# homeboard11.net
KiCad netlist of a schematic drawn in EAGLE
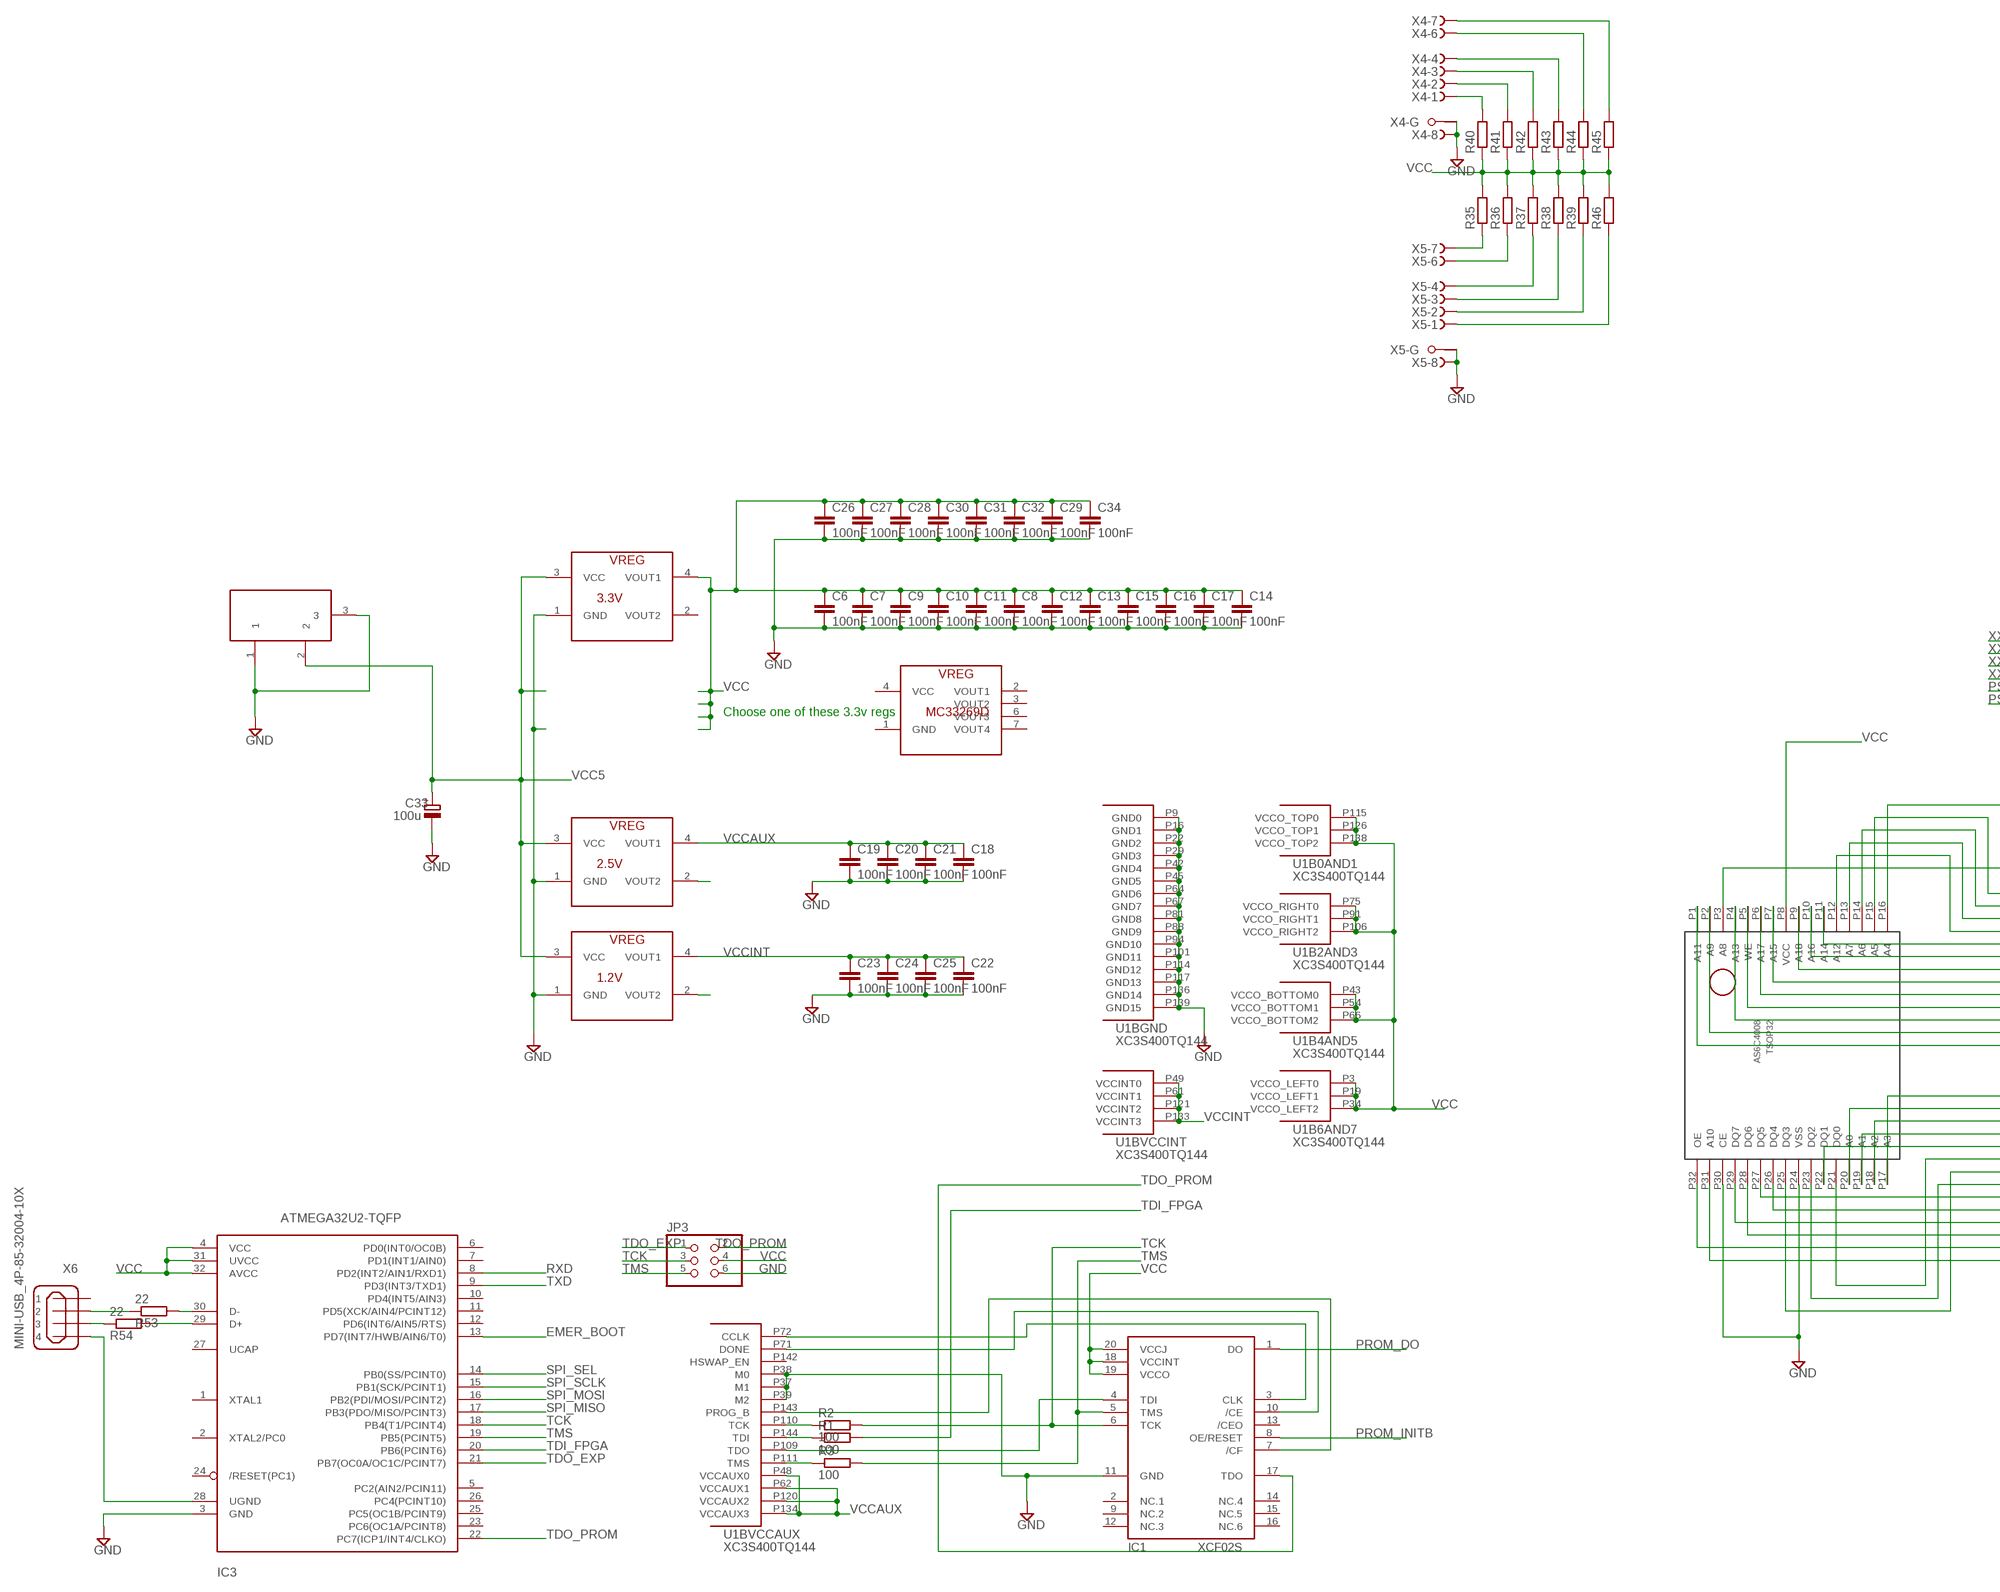
[diagram p0: schematic, sheet 1, part 1 of 3]
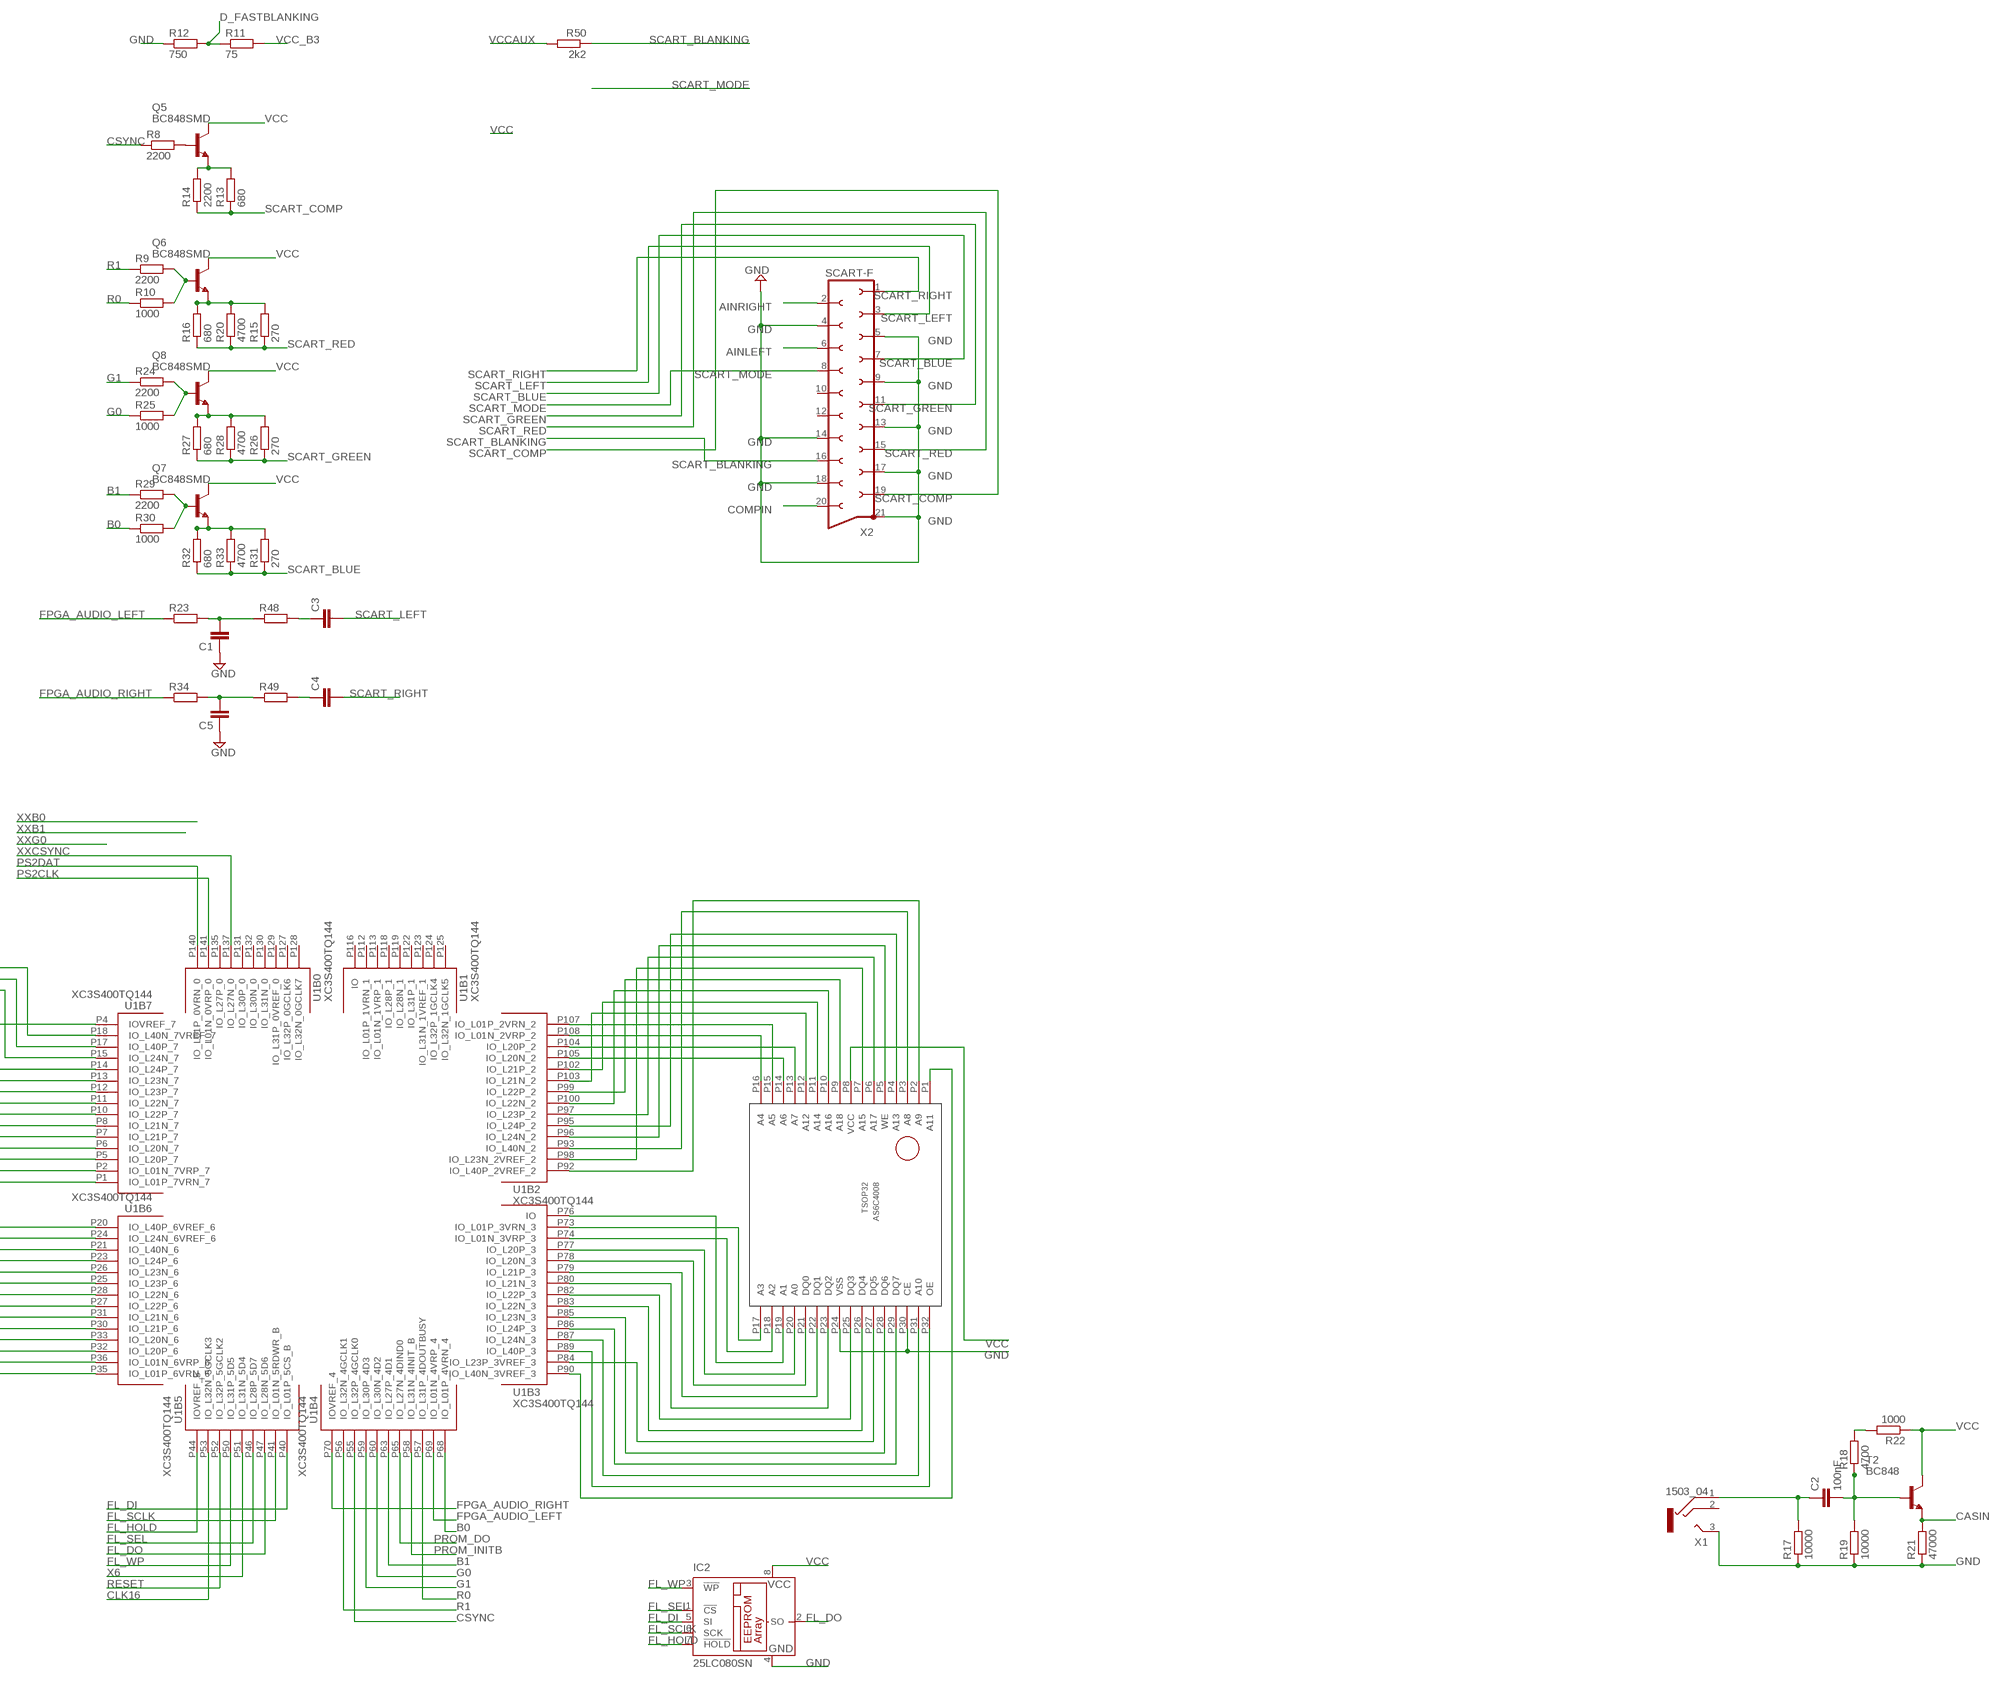
[diagram p1: schematic, sheet 1, part 2 of 3]
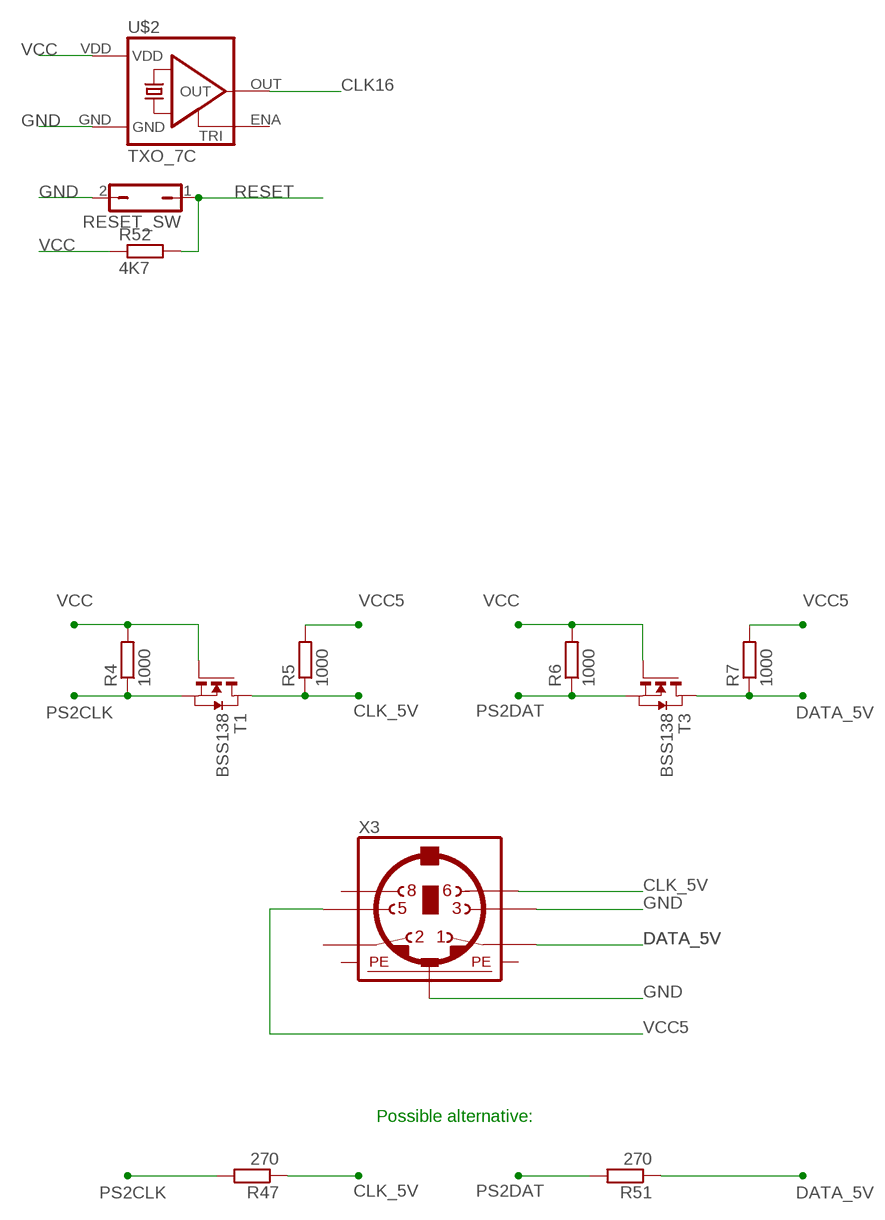
[diagram p2: schematic, sheet 1, part 3 of 3]

(export (version "E")
  (design (tool "Eeschema 10.0.6"))
  (components
    (comp (ref "C1")
      (value "C-EUC0603")
      (footprint "eagle-import:C0603")
      (libsource (lib "eagle-import") (part "resistor_C-EUC0603"))
    )
    (comp (ref "C2")
      (value "100nF")
      (footprint "eagle-import:C0603")
      (libsource (lib "eagle-import") (part "resistor_C-EUC0603"))
    )
    (comp (ref "C3")
      (value "C-EUC0603")
      (footprint "eagle-import:C0603")
      (libsource (lib "eagle-import") (part "resistor_C-EUC0603"))
    )
    (comp (ref "C4")
      (value "C-EUC0603")
      (footprint "eagle-import:C0603")
      (libsource (lib "eagle-import") (part "resistor_C-EUC0603"))
    )
    (comp (ref "C5")
      (value "C-EUC0603")
      (footprint "eagle-import:C0603")
      (libsource (lib "eagle-import") (part "resistor_C-EUC0603"))
    )
    (comp (ref "C6")
      (value "100nF")
      (footprint "eagle-import:C0603")
      (libsource (lib "eagle-import") (part "C-EUC0603"))
    )
    (comp (ref "C7")
      (value "100nF")
      (footprint "eagle-import:C0603")
      (libsource (lib "eagle-import") (part "C-EUC0603"))
    )
    (comp (ref "C8")
      (value "100nF")
      (footprint "eagle-import:C0603")
      (libsource (lib "eagle-import") (part "C-EUC0603"))
    )
    (comp (ref "C9")
      (value "100nF")
      (footprint "eagle-import:C0603")
      (libsource (lib "eagle-import") (part "C-EUC0603"))
    )
    (comp (ref "C10")
      (value "100nF")
      (footprint "eagle-import:C0603")
      (libsource (lib "eagle-import") (part "C-EUC0603"))
    )
    (comp (ref "C11")
      (value "100nF")
      (footprint "eagle-import:C0603")
      (libsource (lib "eagle-import") (part "C-EUC0603"))
    )
    (comp (ref "C12")
      (value "100nF")
      (footprint "eagle-import:C0603")
      (libsource (lib "eagle-import") (part "C-EUC0603"))
    )
    (comp (ref "C13")
      (value "100nF")
      (footprint "eagle-import:C0603")
      (libsource (lib "eagle-import") (part "C-EUC0603"))
    )
    (comp (ref "C14")
      (value "100nF")
      (footprint "eagle-import:C0603")
      (libsource (lib "eagle-import") (part "C-EUC0603"))
    )
    (comp (ref "C15")
      (value "100nF")
      (footprint "eagle-import:C0603")
      (libsource (lib "eagle-import") (part "C-EUC0603"))
    )
    (comp (ref "C16")
      (value "100nF")
      (footprint "eagle-import:C0603")
      (libsource (lib "eagle-import") (part "C-EUC0603"))
    )
    (comp (ref "C17")
      (value "100nF")
      (footprint "eagle-import:C0603")
      (libsource (lib "eagle-import") (part "C-EUC0603"))
    )
    (comp (ref "C18")
      (value "100nF")
      (footprint "eagle-import:C0603")
      (libsource (lib "eagle-import") (part "C-EUC0603"))
    )
    (comp (ref "C19")
      (value "100nF")
      (footprint "eagle-import:C0603")
      (libsource (lib "eagle-import") (part "C-EUC0603"))
    )
    (comp (ref "C20")
      (value "100nF")
      (footprint "eagle-import:C0603")
      (libsource (lib "eagle-import") (part "C-EUC0603"))
    )
    (comp (ref "C21")
      (value "100nF")
      (footprint "eagle-import:C0603")
      (libsource (lib "eagle-import") (part "C-EUC0603"))
    )
    (comp (ref "C22")
      (value "100nF")
      (footprint "eagle-import:C0603")
      (libsource (lib "eagle-import") (part "C-EUC0603"))
    )
    (comp (ref "C23")
      (value "100nF")
      (footprint "eagle-import:C0603")
      (libsource (lib "eagle-import") (part "C-EUC0603"))
    )
    (comp (ref "C24")
      (value "100nF")
      (footprint "eagle-import:C0603")
      (libsource (lib "eagle-import") (part "C-EUC0603"))
    )
    (comp (ref "C25")
      (value "100nF")
      (footprint "eagle-import:C0603")
      (libsource (lib "eagle-import") (part "C-EUC0603"))
    )
    (comp (ref "C26")
      (value "100nF")
      (footprint "eagle-import:C0603")
      (libsource (lib "eagle-import") (part "C-EUC0603"))
    )
    (comp (ref "C27")
      (value "100nF")
      (footprint "eagle-import:C0603")
      (libsource (lib "eagle-import") (part "C-EUC0603"))
    )
    (comp (ref "C28")
      (value "100nF")
      (footprint "eagle-import:C0603")
      (libsource (lib "eagle-import") (part "C-EUC0603"))
    )
    (comp (ref "C29")
      (value "100nF")
      (footprint "eagle-import:C0603")
      (libsource (lib "eagle-import") (part "C-EUC0603"))
    )
    (comp (ref "C30")
      (value "100nF")
      (footprint "eagle-import:C0603")
      (libsource (lib "eagle-import") (part "C-EUC0603"))
    )
    (comp (ref "C31")
      (value "100nF")
      (footprint "eagle-import:C0603")
      (libsource (lib "eagle-import") (part "C-EUC0603"))
    )
    (comp (ref "C32")
      (value "100nF")
      (footprint "eagle-import:C0603")
      (libsource (lib "eagle-import") (part "C-EUC0603"))
    )
    (comp (ref "C33")
      (value "100u")
      (footprint "eagle-import:PANASONIC_D")
      (libsource (lib "eagle-import") (part "CPOL-EUD"))
    )
    (comp (ref "C34")
      (value "100nF")
      (footprint "eagle-import:C0603")
      (libsource (lib "eagle-import") (part "C-EUC0603"))
    )
    (comp (ref "IC1")
      (value "XCF02S")
      (footprint "eagle-import:VO20")
      (libsource (lib "eagle-import") (part "XCF02S"))
    )
    (comp (ref "IC2")
      (value "25LC080SN")
      (footprint "eagle-import:SO-08")
      (fields (field (name "MF") "MICROCHIP") (field (name "MPN") "25LC080/SN"))
      (libsource (lib "eagle-import") (part "25SNLC080"))
    )
    (comp (ref "IC3")
      (value "ATMEGA32U2-TQFP")
      (footprint "eagle-import:TQFP32-08")
      (libsource (lib "eagle-import") (part "ATMEGA32U2-TQFP"))
    )
    (comp (ref "JP3")
      (value "PINHD-2X3")
      (footprint "eagle-import:2X03")
      (libsource (lib "eagle-import") (part "PINHD-2X3"))
    )
    (comp (ref "Q5")
      (value "BC848SMD")
      (footprint "eagle-import:SOT23")
      (libsource (lib "eagle-import") (part "BC848SMD"))
    )
    (comp (ref "Q6")
      (value "BC848SMD")
      (footprint "eagle-import:SOT23")
      (libsource (lib "eagle-import") (part "BC848SMD"))
    )
    (comp (ref "Q7")
      (value "BC848SMD")
      (footprint "eagle-import:SOT23")
      (libsource (lib "eagle-import") (part "BC848SMD"))
    )
    (comp (ref "Q8")
      (value "BC848SMD")
      (footprint "eagle-import:SOT23")
      (libsource (lib "eagle-import") (part "BC848SMD"))
    )
    (comp (ref "R1")
      (value "100")
      (footprint "eagle-import:R0805")
      (libsource (lib "eagle-import") (part "R-EU_R0805"))
    )
    (comp (ref "R2")
      (value "100")
      (footprint "eagle-import:R0805")
      (libsource (lib "eagle-import") (part "R-EU_R0805"))
    )
    (comp (ref "R3")
      (value "100")
      (footprint "eagle-import:R0805")
      (libsource (lib "eagle-import") (part "R-EU_R0805"))
    )
    (comp (ref "R4")
      (value "1000")
      (footprint "eagle-import:R0805")
      (libsource (lib "eagle-import") (part "R-EU_R0805"))
    )
    (comp (ref "R5")
      (value "1000")
      (footprint "eagle-import:R0805")
      (libsource (lib "eagle-import") (part "R-EU_R0805"))
    )
    (comp (ref "R6")
      (value "1000")
      (footprint "eagle-import:R0805")
      (libsource (lib "eagle-import") (part "R-EU_R0805"))
    )
    (comp (ref "R7")
      (value "1000")
      (footprint "eagle-import:R0805")
      (libsource (lib "eagle-import") (part "R-EU_R0805"))
    )
    (comp (ref "R8")
      (value "2200")
      (footprint "eagle-import:R0805")
      (libsource (lib "eagle-import") (part "R-EU_R0805"))
    )
    (comp (ref "R9")
      (value "2200")
      (footprint "eagle-import:R0805")
      (libsource (lib "eagle-import") (part "R-EU_R0805"))
    )
    (comp (ref "R10")
      (value "1000")
      (footprint "eagle-import:R0805")
      (libsource (lib "eagle-import") (part "R-EU_R0805"))
    )
    (comp (ref "R11")
      (value "75")
      (footprint "eagle-import:R0805")
      (libsource (lib "eagle-import") (part "R-EU_R0805"))
    )
    (comp (ref "R12")
      (value "750")
      (footprint "eagle-import:R0805")
      (libsource (lib "eagle-import") (part "R-EU_R0805"))
    )
    (comp (ref "R13")
      (value "680")
      (footprint "eagle-import:R0805")
      (libsource (lib "eagle-import") (part "R-EU_R0805"))
    )
    (comp (ref "R14")
      (value "2200")
      (footprint "eagle-import:R0805")
      (libsource (lib "eagle-import") (part "R-EU_R0805"))
    )
    (comp (ref "R15")
      (value "270")
      (footprint "eagle-import:R0805")
      (libsource (lib "eagle-import") (part "R-EU_R0805"))
    )
    (comp (ref "R16")
      (value "680")
      (footprint "eagle-import:R0805")
      (libsource (lib "eagle-import") (part "R-EU_R0805"))
    )
    (comp (ref "R17")
      (value "10000")
      (footprint "eagle-import:R0805")
      (libsource (lib "eagle-import") (part "R-EU_R0805"))
    )
    (comp (ref "R18")
      (value "4700")
      (footprint "eagle-import:R0805")
      (libsource (lib "eagle-import") (part "R-EU_R0805"))
    )
    (comp (ref "R19")
      (value "10000")
      (footprint "eagle-import:R0805")
      (libsource (lib "eagle-import") (part "R-EU_R0805"))
    )
    (comp (ref "R20")
      (value "4700")
      (footprint "eagle-import:R0805")
      (libsource (lib "eagle-import") (part "R-EU_R0805"))
    )
    (comp (ref "R21")
      (value "47000")
      (footprint "eagle-import:R0805")
      (libsource (lib "eagle-import") (part "R-EU_R0805"))
    )
    (comp (ref "R22")
      (value "1000")
      (footprint "eagle-import:R0805")
      (libsource (lib "eagle-import") (part "R-EU_R0805"))
    )
    (comp (ref "R23")
      (value "R-EU_M0805")
      (footprint "eagle-import:M0805")
      (libsource (lib "eagle-import") (part "resistor_R-EU_M0805"))
    )
    (comp (ref "R24")
      (value "2200")
      (footprint "eagle-import:R0805")
      (libsource (lib "eagle-import") (part "R-EU_R0805"))
    )
    (comp (ref "R25")
      (value "1000")
      (footprint "eagle-import:R0805")
      (libsource (lib "eagle-import") (part "R-EU_R0805"))
    )
    (comp (ref "R26")
      (value "270")
      (footprint "eagle-import:R0805")
      (libsource (lib "eagle-import") (part "R-EU_R0805"))
    )
    (comp (ref "R27")
      (value "680")
      (footprint "eagle-import:R0805")
      (libsource (lib "eagle-import") (part "R-EU_R0805"))
    )
    (comp (ref "R28")
      (value "4700")
      (footprint "eagle-import:R0805")
      (libsource (lib "eagle-import") (part "R-EU_R0805"))
    )
    (comp (ref "R29")
      (value "2200")
      (footprint "eagle-import:R0805")
      (libsource (lib "eagle-import") (part "R-EU_R0805"))
    )
    (comp (ref "R30")
      (value "1000")
      (footprint "eagle-import:R0805")
      (libsource (lib "eagle-import") (part "R-EU_R0805"))
    )
    (comp (ref "R31")
      (value "270")
      (footprint "eagle-import:R0805")
      (libsource (lib "eagle-import") (part "R-EU_R0805"))
    )
    (comp (ref "R32")
      (value "680")
      (footprint "eagle-import:R0805")
      (libsource (lib "eagle-import") (part "R-EU_R0805"))
    )
    (comp (ref "R33")
      (value "4700")
      (footprint "eagle-import:R0805")
      (libsource (lib "eagle-import") (part "R-EU_R0805"))
    )
    (comp (ref "R34")
      (value "R-EU_M0805")
      (footprint "eagle-import:M0805")
      (libsource (lib "eagle-import") (part "resistor_R-EU_M0805"))
    )
    (comp (ref "R35")
      (value "R-EU_M0805")
      (footprint "eagle-import:M0805")
      (libsource (lib "eagle-import") (part "resistor_R-EU_M0805"))
    )
    (comp (ref "R36")
      (value "R-EU_M0805")
      (footprint "eagle-import:M0805")
      (libsource (lib "eagle-import") (part "resistor_R-EU_M0805"))
    )
    (comp (ref "R37")
      (value "R-EU_M0805")
      (footprint "eagle-import:M0805")
      (libsource (lib "eagle-import") (part "resistor_R-EU_M0805"))
    )
    (comp (ref "R38")
      (value "R-EU_M0805")
      (footprint "eagle-import:M0805")
      (libsource (lib "eagle-import") (part "resistor_R-EU_M0805"))
    )
    (comp (ref "R39")
      (value "R-EU_M0805")
      (footprint "eagle-import:M0805")
      (libsource (lib "eagle-import") (part "resistor_R-EU_M0805"))
    )
    (comp (ref "R40")
      (value "R-EU_M0805")
      (footprint "eagle-import:M0805")
      (libsource (lib "eagle-import") (part "resistor_R-EU_M0805"))
    )
    (comp (ref "R41")
      (value "R-EU_M0805")
      (footprint "eagle-import:M0805")
      (libsource (lib "eagle-import") (part "resistor_R-EU_M0805"))
    )
    (comp (ref "R42")
      (value "R-EU_M0805")
      (footprint "eagle-import:M0805")
      (libsource (lib "eagle-import") (part "resistor_R-EU_M0805"))
    )
    (comp (ref "R43")
      (value "R-EU_M0805")
      (footprint "eagle-import:M0805")
      (libsource (lib "eagle-import") (part "resistor_R-EU_M0805"))
    )
    (comp (ref "R44")
      (value "R-EU_M0805")
      (footprint "eagle-import:M0805")
      (libsource (lib "eagle-import") (part "resistor_R-EU_M0805"))
    )
    (comp (ref "R45")
      (value "R-EU_M0805")
      (footprint "eagle-import:M0805")
      (libsource (lib "eagle-import") (part "resistor_R-EU_M0805"))
    )
    (comp (ref "R46")
      (value "R-EU_M0805")
      (footprint "eagle-import:M0805")
      (libsource (lib "eagle-import") (part "resistor_R-EU_M0805"))
    )
    (comp (ref "R47")
      (value "270")
      (footprint "eagle-import:R0805")
      (libsource (lib "eagle-import") (part "R-EU_R0805"))
    )
    (comp (ref "R48")
      (value "R-EU_M0805")
      (footprint "eagle-import:M0805")
      (libsource (lib "eagle-import") (part "resistor_R-EU_M0805"))
    )
    (comp (ref "R49")
      (value "R-EU_M0805")
      (footprint "eagle-import:M0805")
      (libsource (lib "eagle-import") (part "resistor_R-EU_M0805"))
    )
    (comp (ref "R50")
      (value "2k2")
      (footprint "eagle-import:M0805")
      (libsource (lib "eagle-import") (part "resistor_R-EU_M0805"))
    )
    (comp (ref "R51")
      (value "270")
      (footprint "eagle-import:R0805")
      (libsource (lib "eagle-import") (part "R-EU_R0805"))
    )
    (comp (ref "R52")
      (value "4K7")
      (footprint "eagle-import:M0805")
      (libsource (lib "eagle-import") (part "resistor_R-EU_M0805"))
    )
    (comp (ref "R53")
      (value "22")
      (footprint "eagle-import:R0805")
      (libsource (lib "eagle-import") (part "R-EU_R0805"))
    )
    (comp (ref "R54")
      (value "22")
      (footprint "eagle-import:R0805")
      (libsource (lib "eagle-import") (part "R-EU_R0805"))
    )
    (comp (ref "REG1.2")
      (value "1.2V")
      (footprint "eagle-import:SOT223")
      (libsource (lib "eagle-import") (part "NX1117"))
    )
    (comp (ref "REG2.5")
      (value "2.5V")
      (footprint "eagle-import:SOT223")
      (libsource (lib "eagle-import") (part "NX1117"))
    )
    (comp (ref "RESET_SW")
      (value "JP1Q")
      (footprint "eagle-import:JP1")
      (libsource (lib "eagle-import") (part "JP1Q"))
    )
    (comp (ref "T1")
      (value "BSS138")
      (footprint "eagle-import:SOT-23")
      (libsource (lib "eagle-import") (part "NMOSSOT23"))
    )
    (comp (ref "T2")
      (value "BC848")
      (footprint "eagle-import:SOT23")
      (libsource (lib "eagle-import") (part "BC848"))
    )
    (comp (ref "T3")
      (value "BSS138")
      (footprint "eagle-import:SOT-23")
      (libsource (lib "eagle-import") (part "NMOSSOT23"))
    )
    (comp (ref "U$1")
      (value "AS6C4008")
      (footprint "eagle-import:TSOP32")
      (libsource (lib "eagle-import") (part "AS6C4008"))
    )
    (comp (ref "U$2")
      (value "TXO_7C")
      (footprint "eagle-import:OSC_7C")
      (libsource (lib "eagle-import") (part "TXO_7C"))
    )
    (comp (ref "U$4")
      (value "3.3V")
      (footprint "eagle-import:SOT223")
      (libsource (lib "eagle-import") (part "NX1117"))
    )
    (comp (ref "U$5")
      (value "MC33269D")
      (footprint "eagle-import:SO8")
      (libsource (lib "eagle-import") (part "MC33269D"))
    )
    (comp (ref "U$6")
      (value "AS6C4008")
      (footprint "eagle-import:TSOP32")
      (libsource (lib "eagle-import") (part "AS6C4008"))
    )
    (comp (ref "U1")
      (value "XC3S400TQ144")
      (footprint "eagle-import:TQ144")
      (libsource (lib "eagle-import") (part "XC3S400TQ144"))
    )
    (comp (ref "X1")
      (value "1503_04")
      (footprint "eagle-import:1503_04")
      (libsource (lib "eagle-import") (part "1503_04"))
    )
    (comp (ref "X2")
      (value "SCART-F")
      (footprint "eagle-import:SCART-F")
      (libsource (lib "eagle-import") (part "SCART-F"))
    )
    (comp (ref "X3")
      (value "MINI_DIN_6")
      (footprint "eagle-import:M_DIN6")
      (libsource (lib "eagle-import") (part "MINI_DIN_6"))
    )
    (comp (ref "X4")
      (value "F09HPS")
      (footprint "eagle-import:F09HP")
      (libsource (lib "eagle-import") (part "F09HPS"))
    )
    (comp (ref "X5")
      (value "F09HPS")
      (footprint "eagle-import:F09HP")
      (libsource (lib "eagle-import") (part "F09HPS"))
    )
    (comp (ref "X6")
      (value "MINI-USB_4P-85-32004-10X")
      (footprint "eagle-import:85-32004-10X")
      (libsource (lib "eagle-import") (part "MINI-USB_4P-85-32004-10X"))
    )
    (comp (ref "X8")
      (value "DC21MMX")
      (footprint "eagle-import:DC-21MM")
      (libsource (lib "eagle-import") (part "DC21MMX"))
    )
  )
  (nets
    (net (code "1") (name "/AINLEFT") (class "Default")
      (node (ref "X2") (pin "6") (pinfunction "6_6") (pintype "passive"))
    )
    (net (code "2") (name "/AINRIGHT") (class "Default")
      (node (ref "X2") (pin "2") (pinfunction "2_2") (pintype "passive"))
    )
    (net (code "3") (name "/B0") (class "Default")
      (node (ref "R30") (pin "1") (pinfunction "1_1") (pintype "passive"))
      (node (ref "U1") (pin "P68") (pinfunction "IO_L01P_4VRN_4_P68") (pintype "bidirectional"))
    )
    (net (code "4") (name "/B1") (class "Default")
      (node (ref "R29") (pin "1") (pinfunction "1_1") (pintype "passive"))
      (node (ref "U1") (pin "P63") (pinfunction "IO_L27P_4D1_P63") (pintype "bidirectional"))
    )
    (net (code "5") (name "/CASIN") (class "Default")
      (node (ref "R21") (pin "2") (pinfunction "2_2") (pintype "passive"))
      (node (ref "T2") (pin "2") (pinfunction "E_2") (pintype "passive"))
    )
    (net (code "6") (name "/CLK16") (class "Default")
      (node (ref "U$2") (pin "OUT") (pinfunction "OUT_OUT") (pintype "output"))
      (node (ref "U1") (pin "P53") (pinfunction "IO_L32N_5GCLK3_P53") (pintype "bidirectional"))
    )
    (net (code "7") (name "/CLK_5V") (class "Default")
      (node (ref "R47") (pin "1") (pinfunction "1_1") (pintype "passive"))
      (node (ref "R5") (pin "1") (pinfunction "1_1") (pintype "passive"))
      (node (ref "T1") (pin "1") (pinfunction "D_1") (pintype "passive"))
      (node (ref "X3") (pin "6") (pinfunction "6_6") (pintype "passive"))
    )
    (net (code "8") (name "/COMPIN") (class "Default")
      (node (ref "X2") (pin "20") (pinfunction "20_20") (pintype "passive"))
    )
    (net (code "9") (name "/CSYNC") (class "Default")
      (node (ref "R8") (pin "1") (pinfunction "1_1") (pintype "passive"))
      (node (ref "U1") (pin "P55") (pinfunction "IO_L32P_4GCLK0_P55") (pintype "bidirectional"))
    )
    (net (code "10") (name "/DATA_5V") (class "Default")
      (node (ref "R51") (pin "1") (pinfunction "1_1") (pintype "passive"))
      (node (ref "R7") (pin "1") (pinfunction "1_1") (pintype "passive"))
      (node (ref "T3") (pin "1") (pinfunction "D_1") (pintype "passive"))
      (node (ref "X3") (pin "1") (pinfunction "1_1") (pintype "passive"))
    )
    (net (code "11") (name "/D_FASTBLANKING") (class "Default")
      (node (ref "R11") (pin "1") (pinfunction "1_1") (pintype "passive"))
      (node (ref "R12") (pin "2") (pinfunction "2_2") (pintype "passive"))
    )
    (net (code "12") (name "/EMER_BOOT") (class "Default")
      (node (ref "IC3") (pin "13") (pinfunction "PD7(INT7/HWB/AIN6/T0)_13") (pintype "bidirectional"))
    )
    (net (code "13") (name "/FL_DI") (class "Default")
      (node (ref "IC2") (pin "5") (pinfunction "SI_5") (pintype "input"))
      (node (ref "U1") (pin "P40") (pinfunction "IO_L01P_5CS_B_P40") (pintype "bidirectional"))
    )
    (net (code "14") (name "/FL_DO") (class "Default")
      (node (ref "IC2") (pin "2") (pinfunction "SO_2") (pintype "bidirectional"))
      (node (ref "U1") (pin "P47") (pinfunction "IO_L28N_5D6_P47") (pintype "bidirectional"))
    )
    (net (code "15") (name "/FL_HOLD") (class "Default")
      (node (ref "IC2") (pin "7") (pinfunction "~{HOLD}_7") (pintype "input"))
      (node (ref "U1") (pin "P44") (pinfunction "IOVREF_5_P44") (pintype "bidirectional"))
    )
    (net (code "16") (name "/FL_SCLK") (class "Default")
      (node (ref "IC2") (pin "6") (pinfunction "SCK_6") (pintype "input"))
      (node (ref "U1") (pin "P41") (pinfunction "IO_L01N_5RDWR_B_P41") (pintype "bidirectional"))
    )
    (net (code "17") (name "/FL_SEL") (class "Default")
      (node (ref "IC2") (pin "1") (pinfunction "~{CS}_1") (pintype "input"))
      (node (ref "U1") (pin "P46") (pinfunction "IO_L28P_5D7_P46") (pintype "bidirectional"))
    )
    (net (code "18") (name "/FL_WP") (class "Default")
      (node (ref "IC2") (pin "3") (pinfunction "~{WP}_3") (pintype "input"))
      (node (ref "U1") (pin "P50") (pinfunction "IO_L31P_5D5_P50") (pintype "bidirectional"))
    )
    (net (code "19") (name "/FPGA_AUDIO_LEFT") (class "Default")
      (node (ref "R23") (pin "1") (pinfunction "1_1") (pintype "passive"))
      (node (ref "U1") (pin "P69") (pinfunction "IO_L01N_4VRP_4_P69") (pintype "bidirectional"))
    )
    (net (code "20") (name "/FPGA_AUDIO_RIGHT") (class "Default")
      (node (ref "R34") (pin "1") (pinfunction "1_1") (pintype "passive"))
      (node (ref "U1") (pin "P70") (pinfunction "IOVREF_4_P70") (pintype "bidirectional"))
    )
    (net (code "21") (name "/G0") (class "Default")
      (node (ref "R25") (pin "1") (pinfunction "1_1") (pintype "passive"))
      (node (ref "U1") (pin "P60") (pinfunction "IO_L30N_4D2_P60") (pintype "bidirectional"))
    )
    (net (code "22") (name "/G1") (class "Default")
      (node (ref "R24") (pin "1") (pinfunction "1_1") (pintype "passive"))
      (node (ref "U1") (pin "P59") (pinfunction "IO_L30P_4D3_P59") (pintype "bidirectional"))
    )
    (net (code "23") (name "/PE1") (class "Default")
      (node (ref "X3") (pin "SH1") (pinfunction "PE1_SH1") (pintype "power_in"))
    )
    (net (code "24") (name "/PE3") (class "Default")
      (node (ref "X3") (pin "SH3") (pinfunction "PE3_SH3") (pintype "power_in"))
    )
    (net (code "25") (name "/PROM_DO") (class "Default")
      (node (ref "IC1") (pin "1") (pinfunction "DO_1") (pintype "bidirectional"))
      (node (ref "U1") (pin "P65") (pinfunction "IO_L27N_4DIND0_P65") (pintype "bidirectional"))
    )
    (net (code "26") (name "/PROM_INITB") (class "Default")
      (node (ref "IC1") (pin "8") (pinfunction "OE/RESET_8") (pintype "bidirectional"))
      (node (ref "U1") (pin "P58") (pinfunction "IO_L31N_4INIT_B_P58") (pintype "bidirectional"))
    )
    (net (code "27") (name "/PS2CLK") (class "Default")
      (node (ref "R4") (pin "1") (pinfunction "1_1") (pintype "passive"))
      (node (ref "R47") (pin "2") (pinfunction "2_2") (pintype "passive"))
      (node (ref "T1") (pin "2") (pinfunction "S_2") (pintype "passive"))
      (node (ref "U1") (pin "P141") (pinfunction "IO_L01N_0VRP_0_P141") (pintype "bidirectional"))
    )
    (net (code "28") (name "/PS2DAT") (class "Default")
      (node (ref "R51") (pin "2") (pinfunction "2_2") (pintype "passive"))
      (node (ref "R6") (pin "1") (pinfunction "1_1") (pintype "passive"))
      (node (ref "T3") (pin "2") (pinfunction "S_2") (pintype "passive"))
      (node (ref "U1") (pin "P140") (pinfunction "IO_L01P_0VRN_0_P140") (pintype "bidirectional"))
    )
    (net (code "29") (name "/R0") (class "Default")
      (node (ref "R10") (pin "1") (pinfunction "1_1") (pintype "passive"))
      (node (ref "U1") (pin "P57") (pinfunction "IO_L31P_4DOUTBUSY_P57") (pintype "bidirectional"))
    )
    (net (code "30") (name "/R1") (class "Default")
      (node (ref "R9") (pin "1") (pinfunction "1_1") (pintype "passive"))
      (node (ref "U1") (pin "P56") (pinfunction "IO_L32N_4GCLK1_P56") (pintype "bidirectional"))
    )
    (net (code "31") (name "/RESET") (class "Default")
      (node (ref "R52") (pin "2") (pinfunction "2_2") (pintype "passive"))
      (node (ref "RESET_SW") (pin "1") (pinfunction "1_1") (pintype "passive"))
      (node (ref "U1") (pin "P52") (pinfunction "IO_L32P_5GCLK2_P52") (pintype "bidirectional"))
    )
    (net (code "32") (name "/RXD") (class "Default")
      (node (ref "IC3") (pin "8") (pinfunction "PD2(INT2/AIN1/RXD1)_8") (pintype "bidirectional"))
    )
    (net (code "33") (name "/SCART_BLANKING") (class "Default")
      (node (ref "R50") (pin "1") (pinfunction "1_1") (pintype "passive"))
      (node (ref "X2") (pin "16") (pinfunction "16_16") (pintype "passive"))
    )
    (net (code "34") (name "/SCART_BLUE") (class "Default")
      (node (ref "R31") (pin "1") (pinfunction "1_1") (pintype "passive"))
      (node (ref "R32") (pin "1") (pinfunction "1_1") (pintype "passive"))
      (node (ref "R33") (pin "1") (pinfunction "1_1") (pintype "passive"))
      (node (ref "X2") (pin "7") (pinfunction "7_7") (pintype "passive"))
    )
    (net (code "35") (name "/SCART_COMP") (class "Default")
      (node (ref "R13") (pin "1") (pinfunction "1_1") (pintype "passive"))
      (node (ref "R14") (pin "1") (pinfunction "1_1") (pintype "passive"))
      (node (ref "X2") (pin "19") (pinfunction "19_19") (pintype "passive"))
    )
    (net (code "36") (name "/SCART_GREEN") (class "Default")
      (node (ref "R26") (pin "1") (pinfunction "1_1") (pintype "passive"))
      (node (ref "R27") (pin "1") (pinfunction "1_1") (pintype "passive"))
      (node (ref "R28") (pin "1") (pinfunction "1_1") (pintype "passive"))
      (node (ref "X2") (pin "11") (pinfunction "11_11") (pintype "passive"))
    )
    (net (code "37") (name "/SCART_LEFT") (class "Default")
      (node (ref "C3") (pin "2") (pinfunction "2_2") (pintype "passive"))
      (node (ref "X2") (pin "3") (pinfunction "3_3") (pintype "passive"))
    )
    (net (code "38") (name "/SCART_MODE") (class "Default")
      (node (ref "X2") (pin "8") (pinfunction "8_8") (pintype "passive"))
    )
    (net (code "39") (name "/SCART_RED") (class "Default")
      (node (ref "R15") (pin "1") (pinfunction "1_1") (pintype "passive"))
      (node (ref "R16") (pin "1") (pinfunction "1_1") (pintype "passive"))
      (node (ref "R20") (pin "1") (pinfunction "1_1") (pintype "passive"))
      (node (ref "X2") (pin "15") (pinfunction "15_15") (pintype "passive"))
    )
    (net (code "40") (name "/SCART_RIGHT") (class "Default")
      (node (ref "C4") (pin "2") (pinfunction "2_2") (pintype "passive"))
      (node (ref "X2") (pin "1") (pinfunction "1_1") (pintype "passive"))
    )
    (net (code "41") (name "/SPI_MISO") (class "Default")
      (node (ref "IC3") (pin "17") (pinfunction "PB3(PDO/MISO/PCINT3)_17") (pintype "bidirectional"))
    )
    (net (code "42") (name "/SPI_MOSI") (class "Default")
      (node (ref "IC3") (pin "16") (pinfunction "PB2(PDI/MOSI/PCINT2)_16") (pintype "bidirectional"))
    )
    (net (code "43") (name "/SPI_SCLK") (class "Default")
      (node (ref "IC3") (pin "15") (pinfunction "PB1(SCK/PCINT1)_15") (pintype "bidirectional"))
    )
    (net (code "44") (name "/SPI_SEL") (class "Default")
      (node (ref "IC3") (pin "14") (pinfunction "PB0(SS/PCINT0)_14") (pintype "bidirectional"))
    )
    (net (code "45") (name "/TCK") (class "Default")
      (node (ref "IC1") (pin "6") (pinfunction "TCK_6") (pintype "bidirectional"))
      (node (ref "IC3") (pin "18") (pinfunction "PB4(T1/PCINT4)_18") (pintype "bidirectional"))
      (node (ref "JP3") (pin "3") (pinfunction "3_3") (pintype "passive"))
      (node (ref "R2") (pin "2") (pinfunction "2_2") (pintype "passive"))
    )
    (net (code "46") (name "/TDI_FPGA") (class "Default")
      (node (ref "IC3") (pin "20") (pinfunction "PB6(PCINT6)_20") (pintype "bidirectional"))
      (node (ref "R1") (pin "2") (pinfunction "2_2") (pintype "passive"))
    )
    (net (code "47") (name "/TDO_EXP") (class "Default")
      (node (ref "IC3") (pin "21") (pinfunction "PB7(OC0A/OC1C/PCINT7)_21") (pintype "bidirectional"))
      (node (ref "JP3") (pin "1") (pinfunction "1_1") (pintype "passive"))
    )
    (net (code "48") (name "/TDO_PROM") (class "Default")
      (node (ref "IC1") (pin "17") (pinfunction "TDO_17") (pintype "bidirectional"))
      (node (ref "IC3") (pin "22") (pinfunction "PC7(ICP1/INT4/CLKO)_22") (pintype "bidirectional"))
      (node (ref "JP3") (pin "2") (pinfunction "2_2") (pintype "passive"))
    )
    (net (code "49") (name "/TMS") (class "Default")
      (node (ref "IC1") (pin "5") (pinfunction "TMS_5") (pintype "bidirectional"))
      (node (ref "IC3") (pin "19") (pinfunction "PB5(PCINT5)_19") (pintype "bidirectional"))
      (node (ref "JP3") (pin "5") (pinfunction "5_5") (pintype "passive"))
      (node (ref "R3") (pin "2") (pinfunction "2_2") (pintype "passive"))
    )
    (net (code "50") (name "/TXD") (class "Default")
      (node (ref "IC3") (pin "9") (pinfunction "PD3(INT3/TXD1)_9") (pintype "bidirectional"))
    )
    (net (code "51") (name "/VCC") (class "Default")
      (node (ref "C10") (pin "1") (pinfunction "1_1") (pintype "passive"))
      (node (ref "C11") (pin "1") (pinfunction "1_1") (pintype "passive"))
      (node (ref "C12") (pin "1") (pinfunction "1_1") (pintype "passive"))
      (node (ref "C13") (pin "1") (pinfunction "1_1") (pintype "passive"))
      (node (ref "C14") (pin "1") (pinfunction "1_1") (pintype "passive"))
      (node (ref "C15") (pin "1") (pinfunction "1_1") (pintype "passive"))
      (node (ref "C16") (pin "1") (pinfunction "1_1") (pintype "passive"))
      (node (ref "C17") (pin "1") (pinfunction "1_1") (pintype "passive"))
      (node (ref "C26") (pin "1") (pinfunction "1_1") (pintype "passive"))
      (node (ref "C27") (pin "1") (pinfunction "1_1") (pintype "passive"))
      (node (ref "C28") (pin "1") (pinfunction "1_1") (pintype "passive"))
      (node (ref "C29") (pin "1") (pinfunction "1_1") (pintype "passive"))
      (node (ref "C30") (pin "1") (pinfunction "1_1") (pintype "passive"))
      (node (ref "C31") (pin "1") (pinfunction "1_1") (pintype "passive"))
      (node (ref "C32") (pin "1") (pinfunction "1_1") (pintype "passive"))
      (node (ref "C34") (pin "1") (pinfunction "1_1") (pintype "passive"))
      (node (ref "C6") (pin "1") (pinfunction "1_1") (pintype "passive"))
      (node (ref "C7") (pin "1") (pinfunction "1_1") (pintype "passive"))
      (node (ref "C8") (pin "1") (pinfunction "1_1") (pintype "passive"))
      (node (ref "C9") (pin "1") (pinfunction "1_1") (pintype "passive"))
      (node (ref "IC1") (pin "18") (pinfunction "VCCINT_18") (pintype "bidirectional"))
      (node (ref "IC1") (pin "19") (pinfunction "VCCO_19") (pintype "bidirectional"))
      (node (ref "IC1") (pin "20") (pinfunction "VCCJ_20") (pintype "bidirectional"))
      (node (ref "IC2") (pin "8") (pinfunction "VCC_8") (pintype "power_in"))
      (node (ref "IC3") (pin "31") (pinfunction "UVCC_31") (pintype "bidirectional"))
      (node (ref "IC3") (pin "32") (pinfunction "AVCC_32") (pintype "bidirectional"))
      (node (ref "IC3") (pin "4") (pinfunction "VCC_4") (pintype "bidirectional"))
      (node (ref "JP3") (pin "4") (pinfunction "4_4") (pintype "passive"))
      (node (ref "Q5") (pin "3") (pinfunction "C_3") (pintype "passive"))
      (node (ref "Q6") (pin "3") (pinfunction "C_3") (pintype "passive"))
      (node (ref "Q7") (pin "3") (pinfunction "C_3") (pintype "passive"))
      (node (ref "Q8") (pin "3") (pinfunction "C_3") (pintype "passive"))
      (node (ref "R22") (pin "1") (pinfunction "1_1") (pintype "passive"))
      (node (ref "R35") (pin "2") (pinfunction "2_2") (pintype "passive"))
      (node (ref "R36") (pin "2") (pinfunction "2_2") (pintype "passive"))
      (node (ref "R37") (pin "2") (pinfunction "2_2") (pintype "passive"))
      (node (ref "R38") (pin "2") (pinfunction "2_2") (pintype "passive"))
      (node (ref "R39") (pin "2") (pinfunction "2_2") (pintype "passive"))
      (node (ref "R4") (pin "2") (pinfunction "2_2") (pintype "passive"))
      (node (ref "R40") (pin "1") (pinfunction "1_1") (pintype "passive"))
      (node (ref "R41") (pin "1") (pinfunction "1_1") (pintype "passive"))
      (node (ref "R42") (pin "1") (pinfunction "1_1") (pintype "passive"))
      (node (ref "R43") (pin "1") (pinfunction "1_1") (pintype "passive"))
      (node (ref "R44") (pin "1") (pinfunction "1_1") (pintype "passive"))
      (node (ref "R45") (pin "1") (pinfunction "1_1") (pintype "passive"))
      (node (ref "R46") (pin "2") (pinfunction "2_2") (pintype "passive"))
      (node (ref "R52") (pin "1") (pinfunction "1_1") (pintype "passive"))
      (node (ref "R6") (pin "2") (pinfunction "2_2") (pintype "passive"))
      (node (ref "T1") (pin "3") (pinfunction "G_3") (pintype "passive"))
      (node (ref "T2") (pin "3") (pinfunction "C_3") (pintype "passive"))
      (node (ref "T3") (pin "3") (pinfunction "G_3") (pintype "passive"))
      (node (ref "U$1") (pin "P8") (pinfunction "VCC_P8") (pintype "bidirectional"))
      (node (ref "U$2") (pin "VDD") (pinfunction "VDD_VDD") (pintype "power_in"))
      (node (ref "U$4") (pin "4") (pinfunction "VOUT1_4") (pintype "bidirectional"))
      (node (ref "U$6") (pin "P8") (pinfunction "VCC_P8") (pintype "bidirectional"))
      (node (ref "U1") (pin "P106") (pinfunction "VCCO_RIGHT2_P106") (pintype "passive"))
      (node (ref "U1") (pin "P115") (pinfunction "VCCO_TOP0_P115") (pintype "passive"))
      (node (ref "U1") (pin "P126") (pinfunction "VCCO_TOP1_P126") (pintype "passive"))
      (node (ref "U1") (pin "P138") (pinfunction "VCCO_TOP2_P138") (pintype "passive"))
      (node (ref "U1") (pin "P19") (pinfunction "VCCO_LEFT1_P19") (pintype "passive"))
      (node (ref "U1") (pin "P3") (pinfunction "VCCO_LEFT0_P3") (pintype "passive"))
      (node (ref "U1") (pin "P34") (pinfunction "VCCO_LEFT2_P34") (pintype "passive"))
      (node (ref "U1") (pin "P43") (pinfunction "VCCO_BOTTOM0_P43") (pintype "passive"))
      (node (ref "U1") (pin "P54") (pinfunction "VCCO_BOTTOM1_P54") (pintype "passive"))
      (node (ref "U1") (pin "P66") (pinfunction "VCCO_BOTTOM2_P66") (pintype "passive"))
      (node (ref "U1") (pin "P75") (pinfunction "VCCO_RIGHT0_P75") (pintype "passive"))
      (node (ref "U1") (pin "P91") (pinfunction "VCCO_RIGHT1_P91") (pintype "passive"))
    )
    (net (code "52") (name "/VCC5") (class "Default")
      (node (ref "C33") (pin "+") (pinfunction "+_+") (pintype "passive"))
      (node (ref "R5") (pin "2") (pinfunction "2_2") (pintype "passive"))
      (node (ref "R7") (pin "2") (pinfunction "2_2") (pintype "passive"))
      (node (ref "REG1.2") (pin "3") (pinfunction "VCC_3") (pintype "bidirectional"))
      (node (ref "REG2.5") (pin "3") (pinfunction "VCC_3") (pintype "bidirectional"))
      (node (ref "U$4") (pin "3") (pinfunction "VCC_3") (pintype "bidirectional"))
      (node (ref "X3") (pin "5") (pinfunction "5_5") (pintype "passive"))
      (node (ref "X8") (pin "2") (pinfunction "2_2") (pintype "power_in"))
    )
    (net (code "53") (name "/VCCAUX") (class "Default")
      (node (ref "C18") (pin "1") (pinfunction "1_1") (pintype "passive"))
      (node (ref "C19") (pin "1") (pinfunction "1_1") (pintype "passive"))
      (node (ref "C20") (pin "1") (pinfunction "1_1") (pintype "passive"))
      (node (ref "C21") (pin "1") (pinfunction "1_1") (pintype "passive"))
      (node (ref "R50") (pin "2") (pinfunction "2_2") (pintype "passive"))
      (node (ref "REG2.5") (pin "4") (pinfunction "VOUT1_4") (pintype "bidirectional"))
      (node (ref "U1") (pin "P120") (pinfunction "VCCAUX2_P120") (pintype "passive"))
      (node (ref "U1") (pin "P134") (pinfunction "VCCAUX3_P134") (pintype "passive"))
      (node (ref "U1") (pin "P48") (pinfunction "VCCAUX0_P48") (pintype "passive"))
      (node (ref "U1") (pin "P62") (pinfunction "VCCAUX1_P62") (pintype "passive"))
    )
    (net (code "54") (name "/VCCINT") (class "Default")
      (node (ref "C22") (pin "1") (pinfunction "1_1") (pintype "passive"))
      (node (ref "C23") (pin "1") (pinfunction "1_1") (pintype "passive"))
      (node (ref "C24") (pin "1") (pinfunction "1_1") (pintype "passive"))
      (node (ref "C25") (pin "1") (pinfunction "1_1") (pintype "passive"))
      (node (ref "REG1.2") (pin "4") (pinfunction "VOUT1_4") (pintype "bidirectional"))
      (node (ref "U1") (pin "P121") (pinfunction "VCCINT2_P121") (pintype "passive"))
      (node (ref "U1") (pin "P133") (pinfunction "VCCINT3_P133") (pintype "passive"))
      (node (ref "U1") (pin "P49") (pinfunction "VCCINT0_P49") (pintype "passive"))
      (node (ref "U1") (pin "P61") (pinfunction "VCCINT1_P61") (pintype "passive"))
    )
    (net (code "55") (name "/VCC_B3") (class "Default")
      (node (ref "R11") (pin "2") (pinfunction "2_2") (pintype "passive"))
    )
    (net (code "56") (name "/X6") (class "Default")
      (node (ref "U1") (pin "P51") (pinfunction "IO_L31N_5D4_P51") (pintype "bidirectional"))
    )
    (net (code "59") (name "/XXCSYNC") (class "Default")
      (node (ref "U1") (pin "P137") (pinfunction "IO_L27N_0_P137") (pintype "bidirectional"))
    )
    (net (code "61") (name "GND") (class "Default")
      (node (ref "C1") (pin "1") (pinfunction "1_1") (pintype "passive"))
      (node (ref "C10") (pin "2") (pinfunction "2_2") (pintype "passive"))
      (node (ref "C11") (pin "2") (pinfunction "2_2") (pintype "passive"))
      (node (ref "C12") (pin "2") (pinfunction "2_2") (pintype "passive"))
      (node (ref "C13") (pin "2") (pinfunction "2_2") (pintype "passive"))
      (node (ref "C14") (pin "2") (pinfunction "2_2") (pintype "passive"))
      (node (ref "C15") (pin "2") (pinfunction "2_2") (pintype "passive"))
      (node (ref "C16") (pin "2") (pinfunction "2_2") (pintype "passive"))
      (node (ref "C17") (pin "2") (pinfunction "2_2") (pintype "passive"))
      (node (ref "C18") (pin "2") (pinfunction "2_2") (pintype "passive"))
      (node (ref "C19") (pin "2") (pinfunction "2_2") (pintype "passive"))
      (node (ref "C20") (pin "2") (pinfunction "2_2") (pintype "passive"))
      (node (ref "C21") (pin "2") (pinfunction "2_2") (pintype "passive"))
      (node (ref "C22") (pin "2") (pinfunction "2_2") (pintype "passive"))
      (node (ref "C23") (pin "2") (pinfunction "2_2") (pintype "passive"))
      (node (ref "C24") (pin "2") (pinfunction "2_2") (pintype "passive"))
      (node (ref "C25") (pin "2") (pinfunction "2_2") (pintype "passive"))
      (node (ref "C26") (pin "2") (pinfunction "2_2") (pintype "passive"))
      (node (ref "C27") (pin "2") (pinfunction "2_2") (pintype "passive"))
      (node (ref "C28") (pin "2") (pinfunction "2_2") (pintype "passive"))
      (node (ref "C29") (pin "2") (pinfunction "2_2") (pintype "passive"))
      (node (ref "C30") (pin "2") (pinfunction "2_2") (pintype "passive"))
      (node (ref "C31") (pin "2") (pinfunction "2_2") (pintype "passive"))
      (node (ref "C32") (pin "2") (pinfunction "2_2") (pintype "passive"))
      (node (ref "C33") (pin "-") (pinfunction "-_-") (pintype "passive"))
      (node (ref "C34") (pin "2") (pinfunction "2_2") (pintype "passive"))
      (node (ref "C5") (pin "1") (pinfunction "1_1") (pintype "passive"))
      (node (ref "C6") (pin "2") (pinfunction "2_2") (pintype "passive"))
      (node (ref "C7") (pin "2") (pinfunction "2_2") (pintype "passive"))
      (node (ref "C8") (pin "2") (pinfunction "2_2") (pintype "passive"))
      (node (ref "C9") (pin "2") (pinfunction "2_2") (pintype "passive"))
      (node (ref "IC1") (pin "11") (pinfunction "GND_11") (pintype "bidirectional"))
      (node (ref "IC2") (pin "4") (pinfunction "GND_4") (pintype "power_in"))
      (node (ref "IC3") (pin "3") (pinfunction "GND_3") (pintype "bidirectional"))
      (node (ref "JP3") (pin "6") (pinfunction "6_6") (pintype "passive"))
      (node (ref "R12") (pin "1") (pinfunction "1_1") (pintype "passive"))
      (node (ref "R17") (pin "1") (pinfunction "1_1") (pintype "passive"))
      (node (ref "R19") (pin "1") (pinfunction "1_1") (pintype "passive"))
      (node (ref "R21") (pin "1") (pinfunction "1_1") (pintype "passive"))
      (node (ref "REG1.2") (pin "1") (pinfunction "GND_1") (pintype "bidirectional"))
      (node (ref "REG2.5") (pin "1") (pinfunction "GND_1") (pintype "bidirectional"))
      (node (ref "RESET_SW") (pin "2") (pinfunction "2_2") (pintype "passive"))
      (node (ref "U$1") (pin "P24") (pinfunction "VSS_P24") (pintype "bidirectional"))
      (node (ref "U$1") (pin "P30") (pinfunction "CE_P30") (pintype "bidirectional"))
      (node (ref "U$2") (pin "GND") (pinfunction "GND_GND") (pintype "power_in"))
      (node (ref "U$4") (pin "1") (pinfunction "GND_1") (pintype "bidirectional"))
      (node (ref "U$6") (pin "P24") (pinfunction "VSS_P24") (pintype "bidirectional"))
      (node (ref "U$6") (pin "P30") (pinfunction "CE_P30") (pintype "bidirectional"))
      (node (ref "U1") (pin "P101") (pinfunction "GND11_P101") (pintype "passive"))
      (node (ref "U1") (pin "P114") (pinfunction "GND12_P114") (pintype "passive"))
      (node (ref "U1") (pin "P117") (pinfunction "GND13_P117") (pintype "passive"))
      (node (ref "U1") (pin "P136") (pinfunction "GND14_P136") (pintype "passive"))
      (node (ref "U1") (pin "P139") (pinfunction "GND15_P139") (pintype "passive"))
      (node (ref "U1") (pin "P16") (pinfunction "GND1_P16") (pintype "passive"))
      (node (ref "U1") (pin "P22") (pinfunction "GND2_P22") (pintype "passive"))
      (node (ref "U1") (pin "P29") (pinfunction "GND3_P29") (pintype "passive"))
      (node (ref "U1") (pin "P37") (pinfunction "M1_P37") (pintype "bidirectional"))
      (node (ref "U1") (pin "P38") (pinfunction "M0_P38") (pintype "bidirectional"))
      (node (ref "U1") (pin "P39") (pinfunction "M2_P39") (pintype "bidirectional"))
      (node (ref "U1") (pin "P42") (pinfunction "GND4_P42") (pintype "passive"))
      (node (ref "U1") (pin "P45") (pinfunction "GND5_P45") (pintype "passive"))
      (node (ref "U1") (pin "P64") (pinfunction "GND6_P64") (pintype "passive"))
      (node (ref "U1") (pin "P67") (pinfunction "GND7_P67") (pintype "passive"))
      (node (ref "U1") (pin "P81") (pinfunction "GND8_P81") (pintype "passive"))
      (node (ref "U1") (pin "P88") (pinfunction "GND9_P88") (pintype "passive"))
      (node (ref "U1") (pin "P9") (pinfunction "GND0_P9") (pintype "passive"))
      (node (ref "U1") (pin "P94") (pinfunction "GND10_P94") (pintype "passive"))
      (node (ref "X1") (pin "3") (pinfunction "2_3") (pintype "passive"))
      (node (ref "X2") (pin "13") (pinfunction "13_13") (pintype "passive"))
      (node (ref "X2") (pin "14") (pinfunction "14_14") (pintype "passive"))
      (node (ref "X2") (pin "17") (pinfunction "17_17") (pintype "passive"))
      (node (ref "X2") (pin "18") (pinfunction "18_18") (pintype "passive"))
      (node (ref "X2") (pin "21") (pinfunction "21_21") (pintype "passive"))
      (node (ref "X2") (pin "4") (pinfunction "4_4") (pintype "passive"))
      (node (ref "X2") (pin "5") (pinfunction "5_5") (pintype "passive"))
      (node (ref "X2") (pin "9") (pinfunction "9_9") (pintype "passive"))
      (node (ref "X3") (pin "3") (pinfunction "3_3") (pintype "passive"))
      (node (ref "X3") (pin "SH2") (pinfunction "PE2_SH2") (pintype "power_in"))
      (node (ref "X4") (pin "8") (pinfunction "F_8") (pintype "passive"))
      (node (ref "X4") (pin "G1") (pinfunction "G1_G1") (pintype "passive"))
      (node (ref "X5") (pin "8") (pinfunction "F_8") (pintype "passive"))
      (node (ref "X5") (pin "G1") (pinfunction "G1_G1") (pintype "passive"))
      (node (ref "X8") (pin "1") (pinfunction "1_1") (pintype "power_in"))
      (node (ref "X8") (pin "3") (pinfunction "3_3") (pintype "power_in"))
    )
    (net (code "62") (name "Net-(C1-Pad2)") (class "Default")
      (node (ref "C1") (pin "2") (pinfunction "2_2") (pintype "passive"))
      (node (ref "R23") (pin "2") (pinfunction "2_2") (pintype "passive"))
      (node (ref "R48") (pin "1") (pinfunction "1_1") (pintype "passive"))
    )
    (net (code "63") (name "Net-(C2-Pad1)") (class "Default")
      (node (ref "C2") (pin "1") (pinfunction "1_1") (pintype "passive"))
      (node (ref "R17") (pin "2") (pinfunction "2_2") (pintype "passive"))
      (node (ref "X1") (pin "1") (pinfunction "1_1") (pintype "passive"))
    )
    (net (code "64") (name "Net-(C3-Pad1)") (class "Default")
      (node (ref "C3") (pin "1") (pinfunction "1_1") (pintype "passive"))
      (node (ref "R48") (pin "2") (pinfunction "2_2") (pintype "passive"))
    )
    (net (code "65") (name "Net-(C4-Pad1)") (class "Default")
      (node (ref "C4") (pin "1") (pinfunction "1_1") (pintype "passive"))
      (node (ref "R49") (pin "2") (pinfunction "2_2") (pintype "passive"))
    )
    (net (code "66") (name "Net-(C5-Pad2)") (class "Default")
      (node (ref "C5") (pin "2") (pinfunction "2_2") (pintype "passive"))
      (node (ref "R34") (pin "2") (pinfunction "2_2") (pintype "passive"))
      (node (ref "R49") (pin "1") (pinfunction "1_1") (pintype "passive"))
    )
    (net (code "67") (name "Net-(IC1-CLK)") (class "Default")
      (node (ref "IC1") (pin "3") (pinfunction "CLK_3") (pintype "bidirectional"))
      (node (ref "U1") (pin "P72") (pinfunction "CCLK_P72") (pintype "bidirectional"))
    )
    (net (code "68") (name "Net-(IC1-TDI)") (class "Default")
      (node (ref "IC1") (pin "4") (pinfunction "TDI_4") (pintype "bidirectional"))
      (node (ref "U1") (pin "P109") (pinfunction "TDO_P109") (pintype "bidirectional"))
    )
    (net (code "69") (name "Net-(IC1-{slash}CE)") (class "Default")
      (node (ref "IC1") (pin "10") (pinfunction "/CE_10") (pintype "bidirectional"))
      (node (ref "U1") (pin "P71") (pinfunction "DONE_P71") (pintype "bidirectional"))
    )
    (net (code "70") (name "Net-(IC1-{slash}CF)") (class "Default")
      (node (ref "IC1") (pin "7") (pinfunction "/CF_7") (pintype "bidirectional"))
      (node (ref "U1") (pin "P143") (pinfunction "PROG_B_P143") (pintype "bidirectional"))
    )
    (net (code "71") (name "Net-(IC3-D+)") (class "Default")
      (node (ref "IC3") (pin "29") (pinfunction "D+_29") (pintype "bidirectional"))
      (node (ref "R54") (pin "2") (pinfunction "2_2") (pintype "passive"))
    )
    (net (code "72") (name "Net-(IC3-D-)") (class "Default")
      (node (ref "IC3") (pin "30") (pinfunction "D-_30") (pintype "bidirectional"))
      (node (ref "R53") (pin "2") (pinfunction "2_2") (pintype "passive"))
    )
    (net (code "73") (name "Net-(IC3-UGND)") (class "Default")
      (node (ref "IC3") (pin "28") (pinfunction "UGND_28") (pintype "bidirectional"))
      (node (ref "X6") (pin "4") (pinfunction "4_4") (pintype "passive"))
    )
    (net (code "74") (name "Net-(Q5-B)") (class "Default")
      (node (ref "Q5") (pin "1") (pinfunction "B_1") (pintype "passive"))
      (node (ref "R8") (pin "2") (pinfunction "2_2") (pintype "passive"))
    )
    (net (code "75") (name "Net-(Q5-E)") (class "Default")
      (node (ref "Q5") (pin "2") (pinfunction "E_2") (pintype "passive"))
      (node (ref "R13") (pin "2") (pinfunction "2_2") (pintype "passive"))
      (node (ref "R14") (pin "2") (pinfunction "2_2") (pintype "passive"))
    )
    (net (code "76") (name "Net-(Q6-B)") (class "Default")
      (node (ref "Q6") (pin "1") (pinfunction "B_1") (pintype "passive"))
      (node (ref "R10") (pin "2") (pinfunction "2_2") (pintype "passive"))
      (node (ref "R9") (pin "2") (pinfunction "2_2") (pintype "passive"))
    )
    (net (code "77") (name "Net-(Q6-E)") (class "Default")
      (node (ref "Q6") (pin "2") (pinfunction "E_2") (pintype "passive"))
      (node (ref "R15") (pin "2") (pinfunction "2_2") (pintype "passive"))
      (node (ref "R16") (pin "2") (pinfunction "2_2") (pintype "passive"))
      (node (ref "R20") (pin "2") (pinfunction "2_2") (pintype "passive"))
    )
    (net (code "78") (name "Net-(Q7-B)") (class "Default")
      (node (ref "Q7") (pin "1") (pinfunction "B_1") (pintype "passive"))
      (node (ref "R29") (pin "2") (pinfunction "2_2") (pintype "passive"))
      (node (ref "R30") (pin "2") (pinfunction "2_2") (pintype "passive"))
    )
    (net (code "79") (name "Net-(Q7-E)") (class "Default")
      (node (ref "Q7") (pin "2") (pinfunction "E_2") (pintype "passive"))
      (node (ref "R31") (pin "2") (pinfunction "2_2") (pintype "passive"))
      (node (ref "R32") (pin "2") (pinfunction "2_2") (pintype "passive"))
      (node (ref "R33") (pin "2") (pinfunction "2_2") (pintype "passive"))
    )
    (net (code "80") (name "Net-(Q8-B)") (class "Default")
      (node (ref "Q8") (pin "1") (pinfunction "B_1") (pintype "passive"))
      (node (ref "R24") (pin "2") (pinfunction "2_2") (pintype "passive"))
      (node (ref "R25") (pin "2") (pinfunction "2_2") (pintype "passive"))
    )
    (net (code "81") (name "Net-(Q8-E)") (class "Default")
      (node (ref "Q8") (pin "2") (pinfunction "E_2") (pintype "passive"))
      (node (ref "R26") (pin "2") (pinfunction "2_2") (pintype "passive"))
      (node (ref "R27") (pin "2") (pinfunction "2_2") (pintype "passive"))
      (node (ref "R28") (pin "2") (pinfunction "2_2") (pintype "passive"))
    )
    (net (code "82") (name "Net-(R18-Pad2)") (class "Default")
      (node (ref "R18") (pin "2") (pinfunction "2_2") (pintype "passive"))
      (node (ref "R22") (pin "2") (pinfunction "2_2") (pintype "passive"))
    )
    (net (code "83") (name "Net-(R53-Pad1)") (class "Default")
      (node (ref "R53") (pin "1") (pinfunction "1_1") (pintype "passive"))
      (node (ref "X6") (pin "2") (pinfunction "2_2") (pintype "passive"))
    )
    (net (code "84") (name "Net-(R54-Pad1)") (class "Default")
      (node (ref "R54") (pin "1") (pinfunction "1_1") (pintype "passive"))
      (node (ref "X6") (pin "3") (pinfunction "3_3") (pintype "passive"))
    )
    (net (code "85") (name "Net-(T2-B)") (class "Default")
      (node (ref "C2") (pin "2") (pinfunction "2_2") (pintype "passive"))
      (node (ref "R18") (pin "1") (pinfunction "1_1") (pintype "passive"))
      (node (ref "R19") (pin "2") (pinfunction "2_2") (pintype "passive"))
      (node (ref "T2") (pin "1") (pinfunction "B_1") (pintype "passive"))
    )
    (net (code "86") (name "Net-(U$1-A0)") (class "Default")
      (node (ref "U$1") (pin "P20") (pinfunction "A0_P20") (pintype "bidirectional"))
      (node (ref "U1") (pin "P77") (pinfunction "IO_L20P_3_P77") (pintype "bidirectional"))
    )
    (net (code "87") (name "Net-(U$1-A1)") (class "Default")
      (node (ref "U$1") (pin "P19") (pinfunction "A1_P19") (pintype "bidirectional"))
      (node (ref "U1") (pin "P76") (pinfunction "IO_P76") (pintype "bidirectional"))
    )
    (net (code "88") (name "Net-(U$1-A2)") (class "Default")
      (node (ref "U$1") (pin "P18") (pinfunction "A2_P18") (pintype "bidirectional"))
      (node (ref "U1") (pin "P74") (pinfunction "IO_L01N_3VRP_3_P74") (pintype "bidirectional"))
    )
    (net (code "89") (name "Net-(U$1-A3)") (class "Default")
      (node (ref "U$1") (pin "P17") (pinfunction "A3_P17") (pintype "bidirectional"))
      (node (ref "U1") (pin "P73") (pinfunction "IO_L01P_3VRN_3_P73") (pintype "bidirectional"))
    )
    (net (code "90") (name "Net-(U$1-A4)") (class "Default")
      (node (ref "U$1") (pin "P16") (pinfunction "A4_P16") (pintype "bidirectional"))
      (node (ref "U1") (pin "P108") (pinfunction "IO_L01N_2VRP_2_P108") (pintype "bidirectional"))
    )
    (net (code "91") (name "Net-(U$1-A5)") (class "Default")
      (node (ref "U$1") (pin "P15") (pinfunction "A5_P15") (pintype "bidirectional"))
      (node (ref "U1") (pin "P107") (pinfunction "IO_L01P_2VRN_2_P107") (pintype "bidirectional"))
    )
    (net (code "92") (name "Net-(U$1-A6)") (class "Default")
      (node (ref "U$1") (pin "P14") (pinfunction "A6_P14") (pintype "bidirectional"))
      (node (ref "U1") (pin "P105") (pinfunction "IO_L20N_2_P105") (pintype "bidirectional"))
    )
    (net (code "93") (name "Net-(U$1-A7)") (class "Default")
      (node (ref "U$1") (pin "P13") (pinfunction "A7_P13") (pintype "bidirectional"))
      (node (ref "U1") (pin "P104") (pinfunction "IO_L20P_2_P104") (pintype "bidirectional"))
    )
    (net (code "94") (name "Net-(U$1-A8)") (class "Default")
      (node (ref "U$1") (pin "P3") (pinfunction "A8_P3") (pintype "bidirectional"))
      (node (ref "U1") (pin "P93") (pinfunction "IO_L40N_2_P93") (pintype "bidirectional"))
    )
    (net (code "95") (name "Net-(U$1-A9)") (class "Default")
      (node (ref "U$1") (pin "P2") (pinfunction "A9_P2") (pintype "bidirectional"))
      (node (ref "U1") (pin "P92") (pinfunction "IO_L40P_2VREF_2_P92") (pintype "bidirectional"))
    )
    (net (code "96") (name "Net-(U$1-A10)") (class "Default")
      (node (ref "U$1") (pin "P31") (pinfunction "A10_P31") (pintype "bidirectional"))
      (node (ref "U1") (pin "P87") (pinfunction "IO_L24N_3_P87") (pintype "bidirectional"))
    )
    (net (code "97") (name "Net-(U$1-A11)") (class "Default")
      (node (ref "U$1") (pin "P1") (pinfunction "A11_P1") (pintype "bidirectional"))
      (node (ref "U1") (pin "P90") (pinfunction "IO_L40N_3VREF_3_P90") (pintype "bidirectional"))
    )
    (net (code "98") (name "Net-(U$1-A12)") (class "Default")
      (node (ref "U$1") (pin "P12") (pinfunction "A12_P12") (pintype "bidirectional"))
      (node (ref "U1") (pin "P103") (pinfunction "IO_L21N_2_P103") (pintype "bidirectional"))
    )
    (net (code "99") (name "Net-(U$1-A13)") (class "Default")
      (node (ref "U$1") (pin "P4") (pinfunction "A13_P4") (pintype "bidirectional"))
      (node (ref "U1") (pin "P95") (pinfunction "IO_L24P_2_P95") (pintype "bidirectional"))
    )
    (net (code "100") (name "Net-(U$1-A14)") (class "Default")
      (node (ref "U$1") (pin "P11") (pinfunction "A14_P11") (pintype "bidirectional"))
      (node (ref "U1") (pin "P102") (pinfunction "IO_L21P_2_P102") (pintype "bidirectional"))
    )
    (net (code "101") (name "Net-(U$1-A15)") (class "Default")
      (node (ref "U$1") (pin "P7") (pinfunction "A15_P7") (pintype "bidirectional"))
      (node (ref "U1") (pin "P98") (pinfunction "IO_L23N_2VREF_2_P98") (pintype "bidirectional"))
    )
    (net (code "102") (name "Net-(U$1-A16)") (class "Default")
      (node (ref "U$1") (pin "P10") (pinfunction "A16_P10") (pintype "bidirectional"))
      (node (ref "U1") (pin "P100") (pinfunction "IO_L22N_2_P100") (pintype "bidirectional"))
    )
    (net (code "103") (name "Net-(U$1-A17)") (class "Default")
      (node (ref "U$1") (pin "P6") (pinfunction "A17_P6") (pintype "bidirectional"))
      (node (ref "U1") (pin "P97") (pinfunction "IO_L23P_2_P97") (pintype "bidirectional"))
    )
    (net (code "104") (name "Net-(U$1-A18)") (class "Default")
      (node (ref "U$1") (pin "P9") (pinfunction "A18_P9") (pintype "bidirectional"))
      (node (ref "U1") (pin "P99") (pinfunction "IO_L22P_2_P99") (pintype "bidirectional"))
    )
    (net (code "105") (name "Net-(U$1-DQ0)") (class "Default")
      (node (ref "U$1") (pin "P21") (pinfunction "DQ0_P21") (pintype "bidirectional"))
      (node (ref "U1") (pin "P78") (pinfunction "IO_L20N_3_P78") (pintype "bidirectional"))
    )
    (net (code "106") (name "Net-(U$1-DQ1)") (class "Default")
      (node (ref "U$1") (pin "P22") (pinfunction "DQ1_P22") (pintype "bidirectional"))
      (node (ref "U1") (pin "P79") (pinfunction "IO_L21P_3_P79") (pintype "bidirectional"))
    )
    (net (code "107") (name "Net-(U$1-DQ2)") (class "Default")
      (node (ref "U$1") (pin "P23") (pinfunction "DQ2_P23") (pintype "bidirectional"))
      (node (ref "U1") (pin "P80") (pinfunction "IO_L21N_3_P80") (pintype "bidirectional"))
    )
    (net (code "108") (name "Net-(U$1-DQ3)") (class "Default")
      (node (ref "U$1") (pin "P25") (pinfunction "DQ3_P25") (pintype "bidirectional"))
      (node (ref "U1") (pin "P82") (pinfunction "IO_L22P_3_P82") (pintype "bidirectional"))
    )
    (net (code "109") (name "Net-(U$1-DQ4)") (class "Default")
      (node (ref "U$1") (pin "P26") (pinfunction "DQ4_P26") (pintype "bidirectional"))
      (node (ref "U1") (pin "P83") (pinfunction "IO_L22N_3_P83") (pintype "bidirectional"))
    )
    (net (code "110") (name "Net-(U$1-DQ5)") (class "Default")
      (node (ref "U$1") (pin "P27") (pinfunction "DQ5_P27") (pintype "bidirectional"))
      (node (ref "U1") (pin "P84") (pinfunction "IO_L23P_3VREF_3_P84") (pintype "bidirectional"))
    )
    (net (code "111") (name "Net-(U$1-DQ6)") (class "Default")
      (node (ref "U$1") (pin "P28") (pinfunction "DQ6_P28") (pintype "bidirectional"))
      (node (ref "U1") (pin "P85") (pinfunction "IO_L23N_3_P85") (pintype "bidirectional"))
    )
    (net (code "112") (name "Net-(U$1-DQ7)") (class "Default")
      (node (ref "U$1") (pin "P29") (pinfunction "DQ7_P29") (pintype "bidirectional"))
      (node (ref "U1") (pin "P86") (pinfunction "IO_L24P_3_P86") (pintype "bidirectional"))
    )
    (net (code "113") (name "Net-(U$1-OE)") (class "Default")
      (node (ref "U$1") (pin "P32") (pinfunction "OE_P32") (pintype "bidirectional"))
      (node (ref "U1") (pin "P89") (pinfunction "IO_L40P_3_P89") (pintype "bidirectional"))
    )
    (net (code "114") (name "Net-(U$1-WE)") (class "Default")
      (node (ref "U$1") (pin "P5") (pinfunction "WE_P5") (pintype "bidirectional"))
      (node (ref "U1") (pin "P96") (pinfunction "IO_L24N_2_P96") (pintype "bidirectional"))
    )
    (net (code "115") (name "Net-(U$6-A0)") (class "Default")
      (node (ref "U$6") (pin "P20") (pinfunction "A0_P20") (pintype "bidirectional"))
      (node (ref "U1") (pin "P24") (pinfunction "IO_L24N_6VREF_6_P24") (pintype "bidirectional"))
    )
    (net (code "116") (name "Net-(U$6-A1)") (class "Default")
      (node (ref "U$6") (pin "P19") (pinfunction "A1_P19") (pintype "bidirectional"))
      (node (ref "U1") (pin "P23") (pinfunction "IO_L24P_6_P23") (pintype "bidirectional"))
    )
    (net (code "117") (name "Net-(U$6-A2)") (class "Default")
      (node (ref "U$6") (pin "P18") (pinfunction "A2_P18") (pintype "bidirectional"))
      (node (ref "U1") (pin "P21") (pinfunction "IO_L40N_6_P21") (pintype "bidirectional"))
    )
    (net (code "118") (name "Net-(U$6-A3)") (class "Default")
      (node (ref "U$6") (pin "P17") (pinfunction "A3_P17") (pintype "bidirectional"))
      (node (ref "U1") (pin "P20") (pinfunction "IO_L40P_6VREF_6_P20") (pintype "bidirectional"))
    )
    (net (code "119") (name "Net-(U$6-A4)") (class "Default")
      (node (ref "U$6") (pin "P16") (pinfunction "A4_P16") (pintype "bidirectional"))
      (node (ref "U1") (pin "P18") (pinfunction "IO_L40N_7VREF_7_P18") (pintype "bidirectional"))
    )
    (net (code "120") (name "Net-(U$6-A5)") (class "Default")
      (node (ref "U$6") (pin "P15") (pinfunction "A5_P15") (pintype "bidirectional"))
      (node (ref "U1") (pin "P17") (pinfunction "IO_L40P_7_P17") (pintype "bidirectional"))
    )
    (net (code "121") (name "Net-(U$6-A6)") (class "Default")
      (node (ref "U$6") (pin "P14") (pinfunction "A6_P14") (pintype "bidirectional"))
      (node (ref "U1") (pin "P15") (pinfunction "IO_L24N_7_P15") (pintype "bidirectional"))
    )
    (net (code "122") (name "Net-(U$6-A7)") (class "Default")
      (node (ref "U$6") (pin "P13") (pinfunction "A7_P13") (pintype "bidirectional"))
      (node (ref "U1") (pin "P14") (pinfunction "IO_L24P_7_P14") (pintype "bidirectional"))
    )
    (net (code "123") (name "Net-(U$6-A8)") (class "Default")
      (node (ref "U$6") (pin "P3") (pinfunction "A8_P3") (pintype "bidirectional"))
      (node (ref "U1") (pin "P4") (pinfunction "IOVREF_7_P4") (pintype "bidirectional"))
    )
    (net (code "124") (name "Net-(U$6-A9)") (class "Default")
      (node (ref "U$6") (pin "P2") (pinfunction "A9_P2") (pintype "bidirectional"))
      (node (ref "U1") (pin "P2") (pinfunction "IO_L01N_7VRP_7_P2") (pintype "bidirectional"))
    )
    (net (code "125") (name "Net-(U$6-A10)") (class "Default")
      (node (ref "U$6") (pin "P31") (pinfunction "A10_P31") (pintype "bidirectional"))
      (node (ref "U1") (pin "P35") (pinfunction "IO_L01P_6VRN_6_P35") (pintype "bidirectional"))
    )
    (net (code "126") (name "Net-(U$6-A11)") (class "Default")
      (node (ref "U$6") (pin "P1") (pinfunction "A11_P1") (pintype "bidirectional"))
      (node (ref "U1") (pin "P1") (pinfunction "IO_L01P_7VRN_7_P1") (pintype "bidirectional"))
    )
    (net (code "127") (name "Net-(U$6-A12)") (class "Default")
      (node (ref "U$6") (pin "P12") (pinfunction "A12_P12") (pintype "bidirectional"))
      (node (ref "U1") (pin "P13") (pinfunction "IO_L23N_7_P13") (pintype "bidirectional"))
    )
    (net (code "128") (name "Net-(U$6-A13)") (class "Default")
      (node (ref "U$6") (pin "P4") (pinfunction "A13_P4") (pintype "bidirectional"))
      (node (ref "U1") (pin "P5") (pinfunction "IO_L20P_7_P5") (pintype "bidirectional"))
    )
    (net (code "129") (name "Net-(U$6-A14)") (class "Default")
      (node (ref "U$6") (pin "P11") (pinfunction "A14_P11") (pintype "bidirectional"))
      (node (ref "U1") (pin "P12") (pinfunction "IO_L23P_7_P12") (pintype "bidirectional"))
    )
    (net (code "130") (name "Net-(U$6-A15)") (class "Default")
      (node (ref "U$6") (pin "P7") (pinfunction "A15_P7") (pintype "bidirectional"))
      (node (ref "U1") (pin "P8") (pinfunction "IO_L21N_7_P8") (pintype "bidirectional"))
    )
    (net (code "131") (name "Net-(U$6-A16)") (class "Default")
      (node (ref "U$6") (pin "P10") (pinfunction "A16_P10") (pintype "bidirectional"))
      (node (ref "U1") (pin "P11") (pinfunction "IO_L22N_7_P11") (pintype "bidirectional"))
    )
    (net (code "132") (name "Net-(U$6-A17)") (class "Default")
      (node (ref "U$6") (pin "P6") (pinfunction "A17_P6") (pintype "bidirectional"))
      (node (ref "U1") (pin "P7") (pinfunction "IO_L21P_7_P7") (pintype "bidirectional"))
    )
    (net (code "133") (name "Net-(U$6-A18)") (class "Default")
      (node (ref "U$6") (pin "P9") (pinfunction "A18_P9") (pintype "bidirectional"))
      (node (ref "U1") (pin "P10") (pinfunction "IO_L22P_7_P10") (pintype "bidirectional"))
    )
    (net (code "134") (name "Net-(U$6-DQ0)") (class "Default")
      (node (ref "U$6") (pin "P21") (pinfunction "DQ0_P21") (pintype "bidirectional"))
      (node (ref "U1") (pin "P25") (pinfunction "IO_L23P_6_P25") (pintype "bidirectional"))
    )
    (net (code "135") (name "Net-(U$6-DQ1)") (class "Default")
      (node (ref "U$6") (pin "P22") (pinfunction "DQ1_P22") (pintype "bidirectional"))
      (node (ref "U1") (pin "P26") (pinfunction "IO_L23N_6_P26") (pintype "bidirectional"))
    )
    (net (code "136") (name "Net-(U$6-DQ2)") (class "Default")
      (node (ref "U$6") (pin "P23") (pinfunction "DQ2_P23") (pintype "bidirectional"))
      (node (ref "U1") (pin "P27") (pinfunction "IO_L22P_6_P27") (pintype "bidirectional"))
    )
    (net (code "137") (name "Net-(U$6-DQ3)") (class "Default")
      (node (ref "U$6") (pin "P25") (pinfunction "DQ3_P25") (pintype "bidirectional"))
      (node (ref "U1") (pin "P28") (pinfunction "IO_L22N_6_P28") (pintype "bidirectional"))
    )
    (net (code "138") (name "Net-(U$6-DQ4)") (class "Default")
      (node (ref "U$6") (pin "P26") (pinfunction "DQ4_P26") (pintype "bidirectional"))
      (node (ref "U1") (pin "P30") (pinfunction "IO_L21P_6_P30") (pintype "bidirectional"))
    )
    (net (code "139") (name "Net-(U$6-DQ5)") (class "Default")
      (node (ref "U$6") (pin "P27") (pinfunction "DQ5_P27") (pintype "bidirectional"))
      (node (ref "U1") (pin "P31") (pinfunction "IO_L21N_6_P31") (pintype "bidirectional"))
    )
    (net (code "140") (name "Net-(U$6-DQ6)") (class "Default")
      (node (ref "U$6") (pin "P28") (pinfunction "DQ6_P28") (pintype "bidirectional"))
      (node (ref "U1") (pin "P32") (pinfunction "IO_L20P_6_P32") (pintype "bidirectional"))
    )
    (net (code "141") (name "Net-(U$6-DQ7)") (class "Default")
      (node (ref "U$6") (pin "P29") (pinfunction "DQ7_P29") (pintype "bidirectional"))
      (node (ref "U1") (pin "P33") (pinfunction "IO_L20N_6_P33") (pintype "bidirectional"))
    )
    (net (code "142") (name "Net-(U$6-OE)") (class "Default")
      (node (ref "U$6") (pin "P32") (pinfunction "OE_P32") (pintype "bidirectional"))
      (node (ref "U1") (pin "P36") (pinfunction "IO_L01N_6VRP_6_P36") (pintype "bidirectional"))
    )
    (net (code "143") (name "Net-(U$6-WE)") (class "Default")
      (node (ref "U$6") (pin "P5") (pinfunction "WE_P5") (pintype "bidirectional"))
      (node (ref "U1") (pin "P6") (pinfunction "IO_L20N_7_P6") (pintype "bidirectional"))
    )
    (net (code "144") (name "Net-(U1N-TCK)") (class "Default")
      (node (ref "R2") (pin "1") (pinfunction "1_1") (pintype "passive"))
      (node (ref "U1") (pin "P110") (pinfunction "TCK_P110") (pintype "bidirectional"))
    )
    (net (code "145") (name "Net-(U1N-TDI)") (class "Default")
      (node (ref "R1") (pin "1") (pinfunction "1_1") (pintype "passive"))
      (node (ref "U1") (pin "P144") (pinfunction "TDI_P144") (pintype "bidirectional"))
    )
    (net (code "146") (name "Net-(U1N-TMS)") (class "Default")
      (node (ref "R3") (pin "1") (pinfunction "1_1") (pintype "passive"))
      (node (ref "U1") (pin "P111") (pinfunction "TMS_P111") (pintype "bidirectional"))
    )
    (net (code "147") (name "Net-(X4A-F)") (class "Default")
      (node (ref "R40") (pin "2") (pinfunction "2_2") (pintype "passive"))
      (node (ref "X4") (pin "1") (pinfunction "F_1") (pintype "passive"))
    )
    (net (code "148") (name "Net-(X4B-F)") (class "Default")
      (node (ref "R41") (pin "2") (pinfunction "2_2") (pintype "passive"))
      (node (ref "X4") (pin "2") (pinfunction "F_2") (pintype "passive"))
    )
    (net (code "149") (name "Net-(X4C-F)") (class "Default")
      (node (ref "R42") (pin "2") (pinfunction "2_2") (pintype "passive"))
      (node (ref "X4") (pin "3") (pinfunction "F_3") (pintype "passive"))
    )
    (net (code "150") (name "Net-(X4D-F)") (class "Default")
      (node (ref "R43") (pin "2") (pinfunction "2_2") (pintype "passive"))
      (node (ref "X4") (pin "4") (pinfunction "F_4") (pintype "passive"))
    )
    (net (code "151") (name "Net-(X4F-F)") (class "Default")
      (node (ref "R44") (pin "2") (pinfunction "2_2") (pintype "passive"))
      (node (ref "X4") (pin "6") (pinfunction "F_6") (pintype "passive"))
    )
    (net (code "152") (name "Net-(X4G-F)") (class "Default")
      (node (ref "R45") (pin "2") (pinfunction "2_2") (pintype "passive"))
      (node (ref "X4") (pin "7") (pinfunction "F_7") (pintype "passive"))
    )
    (net (code "153") (name "Net-(X5A-F)") (class "Default")
      (node (ref "R46") (pin "1") (pinfunction "1_1") (pintype "passive"))
      (node (ref "X5") (pin "1") (pinfunction "F_1") (pintype "passive"))
    )
    (net (code "154") (name "Net-(X5B-F)") (class "Default")
      (node (ref "R39") (pin "1") (pinfunction "1_1") (pintype "passive"))
      (node (ref "X5") (pin "2") (pinfunction "F_2") (pintype "passive"))
    )
    (net (code "155") (name "Net-(X5C-F)") (class "Default")
      (node (ref "R38") (pin "1") (pinfunction "1_1") (pintype "passive"))
      (node (ref "X5") (pin "3") (pinfunction "F_3") (pintype "passive"))
    )
    (net (code "156") (name "Net-(X5D-F)") (class "Default")
      (node (ref "R37") (pin "1") (pinfunction "1_1") (pintype "passive"))
      (node (ref "X5") (pin "4") (pinfunction "F_4") (pintype "passive"))
    )
    (net (code "157") (name "Net-(X5F-F)") (class "Default")
      (node (ref "R36") (pin "1") (pinfunction "1_1") (pintype "passive"))
      (node (ref "X5") (pin "6") (pinfunction "F_6") (pintype "passive"))
    )
    (net (code "158") (name "Net-(X5G-F)") (class "Default")
      (node (ref "R35") (pin "1") (pinfunction "1_1") (pintype "passive"))
      (node (ref "X5") (pin "7") (pinfunction "F_7") (pintype "passive"))
    )
    (net (code "159") (name "unconnected-(IC1-NC.1-Pad2)") (class "Default")
      (node (ref "IC1") (pin "2") (pinfunction "NC.1_2") (pintype "bidirectional"))
    )
    (net (code "160") (name "unconnected-(IC1-NC.2-Pad9)") (class "Default")
      (node (ref "IC1") (pin "9") (pinfunction "NC.2_9") (pintype "bidirectional"))
    )
    (net (code "161") (name "unconnected-(IC1-NC.3-Pad12)") (class "Default")
      (node (ref "IC1") (pin "12") (pinfunction "NC.3_12") (pintype "bidirectional"))
    )
    (net (code "162") (name "unconnected-(IC1-NC.4-Pad14)") (class "Default")
      (node (ref "IC1") (pin "14") (pinfunction "NC.4_14") (pintype "bidirectional"))
    )
    (net (code "163") (name "unconnected-(IC1-NC.5-Pad15)") (class "Default")
      (node (ref "IC1") (pin "15") (pinfunction "NC.5_15") (pintype "bidirectional"))
    )
    (net (code "164") (name "unconnected-(IC1-NC.6-Pad16)") (class "Default")
      (node (ref "IC1") (pin "16") (pinfunction "NC.6_16") (pintype "bidirectional"))
    )
    (net (code "165") (name "unconnected-(IC1-{slash}CEO-Pad13)") (class "Default")
      (node (ref "IC1") (pin "13") (pinfunction "/CEO_13") (pintype "bidirectional"))
    )
    (net (code "166") (name "unconnected-(IC3-PC2(AIN2{slash}PCIN11)-Pad5)") (class "Default")
      (node (ref "IC3") (pin "5") (pinfunction "PC2(AIN2/PCIN11)_5") (pintype "bidirectional"))
    )
    (net (code "167") (name "unconnected-(IC3-PC4(PCINT10)-Pad26)") (class "Default")
      (node (ref "IC3") (pin "26") (pinfunction "PC4(PCINT10)_26") (pintype "bidirectional"))
    )
    (net (code "168") (name "unconnected-(IC3-PC5(OC1B{slash}PCINT9)-Pad25)") (class "Default")
      (node (ref "IC3") (pin "25") (pinfunction "PC5(OC1B/PCINT9)_25") (pintype "bidirectional"))
    )
    (net (code "169") (name "unconnected-(IC3-PC6(OC1A{slash}PCINT8)-Pad23)") (class "Default")
      (node (ref "IC3") (pin "23") (pinfunction "PC6(OC1A/PCINT8)_23") (pintype "bidirectional"))
    )
    (net (code "170") (name "unconnected-(IC3-PD0(INT0{slash}OC0B)-Pad6)") (class "Default")
      (node (ref "IC3") (pin "6") (pinfunction "PD0(INT0/OC0B)_6") (pintype "bidirectional"))
    )
    (net (code "171") (name "unconnected-(IC3-PD1(INT1{slash}AIN0)-Pad7)") (class "Default")
      (node (ref "IC3") (pin "7") (pinfunction "PD1(INT1/AIN0)_7") (pintype "bidirectional"))
    )
    (net (code "172") (name "unconnected-(IC3-PD4(INT5{slash}AIN3)-Pad10)") (class "Default")
      (node (ref "IC3") (pin "10") (pinfunction "PD4(INT5/AIN3)_10") (pintype "bidirectional"))
    )
    (net (code "173") (name "unconnected-(IC3-PD5(XCK{slash}AIN4{slash}PCINT12)-Pad11)") (class "Default")
      (node (ref "IC3") (pin "11") (pinfunction "PD5(XCK/AIN4/PCINT12)_11") (pintype "bidirectional"))
    )
    (net (code "174") (name "unconnected-(IC3-PD6(INT6{slash}AIN5{slash}RTS)-Pad12)") (class "Default")
      (node (ref "IC3") (pin "12") (pinfunction "PD6(INT6/AIN5/RTS)_12") (pintype "bidirectional"))
    )
    (net (code "175") (name "unconnected-(IC3-UCAP-Pad27)") (class "Default")
      (node (ref "IC3") (pin "27") (pinfunction "UCAP_27") (pintype "bidirectional"))
    )
    (net (code "176") (name "unconnected-(IC3-XTAL1-Pad1)") (class "Default")
      (node (ref "IC3") (pin "1") (pinfunction "XTAL1_1") (pintype "bidirectional"))
    )
    (net (code "177") (name "unconnected-(IC3-XTAL2{slash}PC0-Pad2)") (class "Default")
      (node (ref "IC3") (pin "2") (pinfunction "XTAL2/PC0_2") (pintype "bidirectional"))
    )
    (net (code "178") (name "unconnected-(IC3-{slash}RESET(PC1)-Pad24)") (class "Default")
      (node (ref "IC3") (pin "24") (pinfunction "/RESET(PC1)_24") (pintype "bidirectional"))
    )
    (net (code "179") (name "unconnected-(REG1.2-VOUT2-Pad2)") (class "Default")
      (node (ref "REG1.2") (pin "2") (pinfunction "VOUT2_2") (pintype "bidirectional"))
    )
    (net (code "180") (name "unconnected-(REG2.5-VOUT2-Pad2)") (class "Default")
      (node (ref "REG2.5") (pin "2") (pinfunction "VOUT2_2") (pintype "bidirectional"))
    )
    (net (code "181") (name "unconnected-(U$2-TRI-PadENA)") (class "Default")
      (node (ref "U$2") (pin "ENA") (pinfunction "TRI_ENA") (pintype "input"))
    )
    (net (code "182") (name "unconnected-(U$4-VOUT2-Pad2)") (class "Default")
      (node (ref "U$4") (pin "2") (pinfunction "VOUT2_2") (pintype "bidirectional"))
    )
    (net (code "183") (name "unconnected-(U$5-GND-Pad1)") (class "Default")
      (node (ref "U$5") (pin "1") (pinfunction "GND_1") (pintype "bidirectional"))
    )
    (net (code "184") (name "unconnected-(U$5-VCC-Pad4)") (class "Default")
      (node (ref "U$5") (pin "4") (pinfunction "VCC_4") (pintype "bidirectional"))
    )
    (net (code "185") (name "unconnected-(U$5-VOUT1-Pad2)") (class "Default")
      (node (ref "U$5") (pin "2") (pinfunction "VOUT1_2") (pintype "output"))
    )
    (net (code "186") (name "unconnected-(U$5-VOUT2-Pad3)") (class "Default")
      (node (ref "U$5") (pin "3") (pinfunction "VOUT2_3") (pintype "output"))
    )
    (net (code "187") (name "unconnected-(U$5-VOUT3-Pad6)") (class "Default")
      (node (ref "U$5") (pin "6") (pinfunction "VOUT3_6") (pintype "output"))
    )
    (net (code "188") (name "unconnected-(U$5-VOUT4-Pad7)") (class "Default")
      (node (ref "U$5") (pin "7") (pinfunction "VOUT4_7") (pintype "output"))
    )
    (net (code "189") (name "unconnected-(U1A-IO_L27P_0-PadP135)") (class "Default")
      (node (ref "U1") (pin "P135") (pinfunction "IO_L27P_0_P135") (pintype "bidirectional"))
    )
    (net (code "190") (name "unconnected-(U1A-IO_L30N_0-PadP132)") (class "Default")
      (node (ref "U1") (pin "P132") (pinfunction "IO_L30N_0_P132") (pintype "bidirectional"))
    )
    (net (code "191") (name "unconnected-(U1A-IO_L30P_0-PadP131)") (class "Default")
      (node (ref "U1") (pin "P131") (pinfunction "IO_L30P_0_P131") (pintype "bidirectional"))
    )
    (net (code "192") (name "unconnected-(U1A-IO_L31N_0-PadP130)") (class "Default")
      (node (ref "U1") (pin "P130") (pinfunction "IO_L31N_0_P130") (pintype "bidirectional"))
    )
    (net (code "193") (name "unconnected-(U1A-IO_L31P_0VREF_0-PadP129)") (class "Default")
      (node (ref "U1") (pin "P129") (pinfunction "IO_L31P_0VREF_0_P129") (pintype "bidirectional"))
    )
    (net (code "194") (name "unconnected-(U1A-IO_L32N_0GCLK7-PadP128)") (class "Default")
      (node (ref "U1") (pin "P128") (pinfunction "IO_L32N_0GCLK7_P128") (pintype "bidirectional"))
    )
    (net (code "195") (name "unconnected-(U1A-IO_L32P_0GCLK6-PadP127)") (class "Default")
      (node (ref "U1") (pin "P127") (pinfunction "IO_L32P_0GCLK6_P127") (pintype "bidirectional"))
    )
    (net (code "196") (name "unconnected-(U1C-IO-PadP116)") (class "Default")
      (node (ref "U1") (pin "P116") (pinfunction "IO_P116") (pintype "bidirectional"))
    )
    (net (code "197") (name "unconnected-(U1C-IO_L01N_1VRP_1-PadP113)") (class "Default")
      (node (ref "U1") (pin "P113") (pinfunction "IO_L01N_1VRP_1_P113") (pintype "bidirectional"))
    )
    (net (code "198") (name "unconnected-(U1C-IO_L01P_1VRN_1-PadP112)") (class "Default")
      (node (ref "U1") (pin "P112") (pinfunction "IO_L01P_1VRN_1_P112") (pintype "bidirectional"))
    )
    (net (code "199") (name "unconnected-(U1C-IO_L28N_1-PadP119)") (class "Default")
      (node (ref "U1") (pin "P119") (pinfunction "IO_L28N_1_P119") (pintype "bidirectional"))
    )
    (net (code "200") (name "unconnected-(U1C-IO_L28P_1-PadP118)") (class "Default")
      (node (ref "U1") (pin "P118") (pinfunction "IO_L28P_1_P118") (pintype "bidirectional"))
    )
    (net (code "201") (name "unconnected-(U1C-IO_L31N_1VREF_1-PadP123)") (class "Default")
      (node (ref "U1") (pin "P123") (pinfunction "IO_L31N_1VREF_1_P123") (pintype "bidirectional"))
    )
    (net (code "202") (name "unconnected-(U1C-IO_L31P_1-PadP122)") (class "Default")
      (node (ref "U1") (pin "P122") (pinfunction "IO_L31P_1_P122") (pintype "bidirectional"))
    )
    (net (code "203") (name "unconnected-(U1C-IO_L32N_1GCLK5-PadP125)") (class "Default")
      (node (ref "U1") (pin "P125") (pinfunction "IO_L32N_1GCLK5_P125") (pintype "bidirectional"))
    )
    (net (code "204") (name "unconnected-(U1C-IO_L32P_1GCLK4-PadP124)") (class "Default")
      (node (ref "U1") (pin "P124") (pinfunction "IO_L32P_1GCLK4_P124") (pintype "bidirectional"))
    )
    (net (code "205") (name "unconnected-(U1N-HSWAP_EN-PadP142)") (class "Default")
      (node (ref "U1") (pin "P142") (pinfunction "HSWAP_EN_P142") (pintype "bidirectional"))
    )
    (net (code "206") (name "unconnected-(X1-3-Pad2)") (class "Default")
      (node (ref "X1") (pin "2") (pinfunction "3_2") (pintype "passive"))
    )
    (net (code "207") (name "unconnected-(X2-Pad10)") (class "Default")
      (node (ref "X2") (pin "10") (pinfunction "10_10") (pintype "passive"))
    )
    (net (code "208") (name "unconnected-(X2-Pad12)") (class "Default")
      (node (ref "X2") (pin "12") (pinfunction "12_12") (pintype "passive"))
    )
    (net (code "209") (name "unconnected-(X3-Pad2)") (class "Default")
      (node (ref "X3") (pin "2") (pinfunction "2_2") (pintype "passive"))
    )
    (net (code "210") (name "unconnected-(X3-Pad8)") (class "Default")
      (node (ref "X3") (pin "8") (pinfunction "8_8") (pintype "passive"))
    )
    (net (code "211") (name "unconnected-(X4-PadG2)") (class "Default")
      (node (ref "X4") (pin "G2") (pinfunction "G2_G2") (pintype "passive"))
    )
    (net (code "212") (name "unconnected-(X5-PadG2)") (class "Default")
      (node (ref "X5") (pin "G2") (pinfunction "G2_G2") (pintype "passive"))
    )
    (net (code "213") (name "unconnected-(X6-Pad1)") (class "Default")
      (node (ref "X6") (pin "1") (pinfunction "1_1") (pintype "passive"))
    )
  )
)
